# REM_Scan_v2.net
KiCad netlist of a schematic drawn in EAGLE
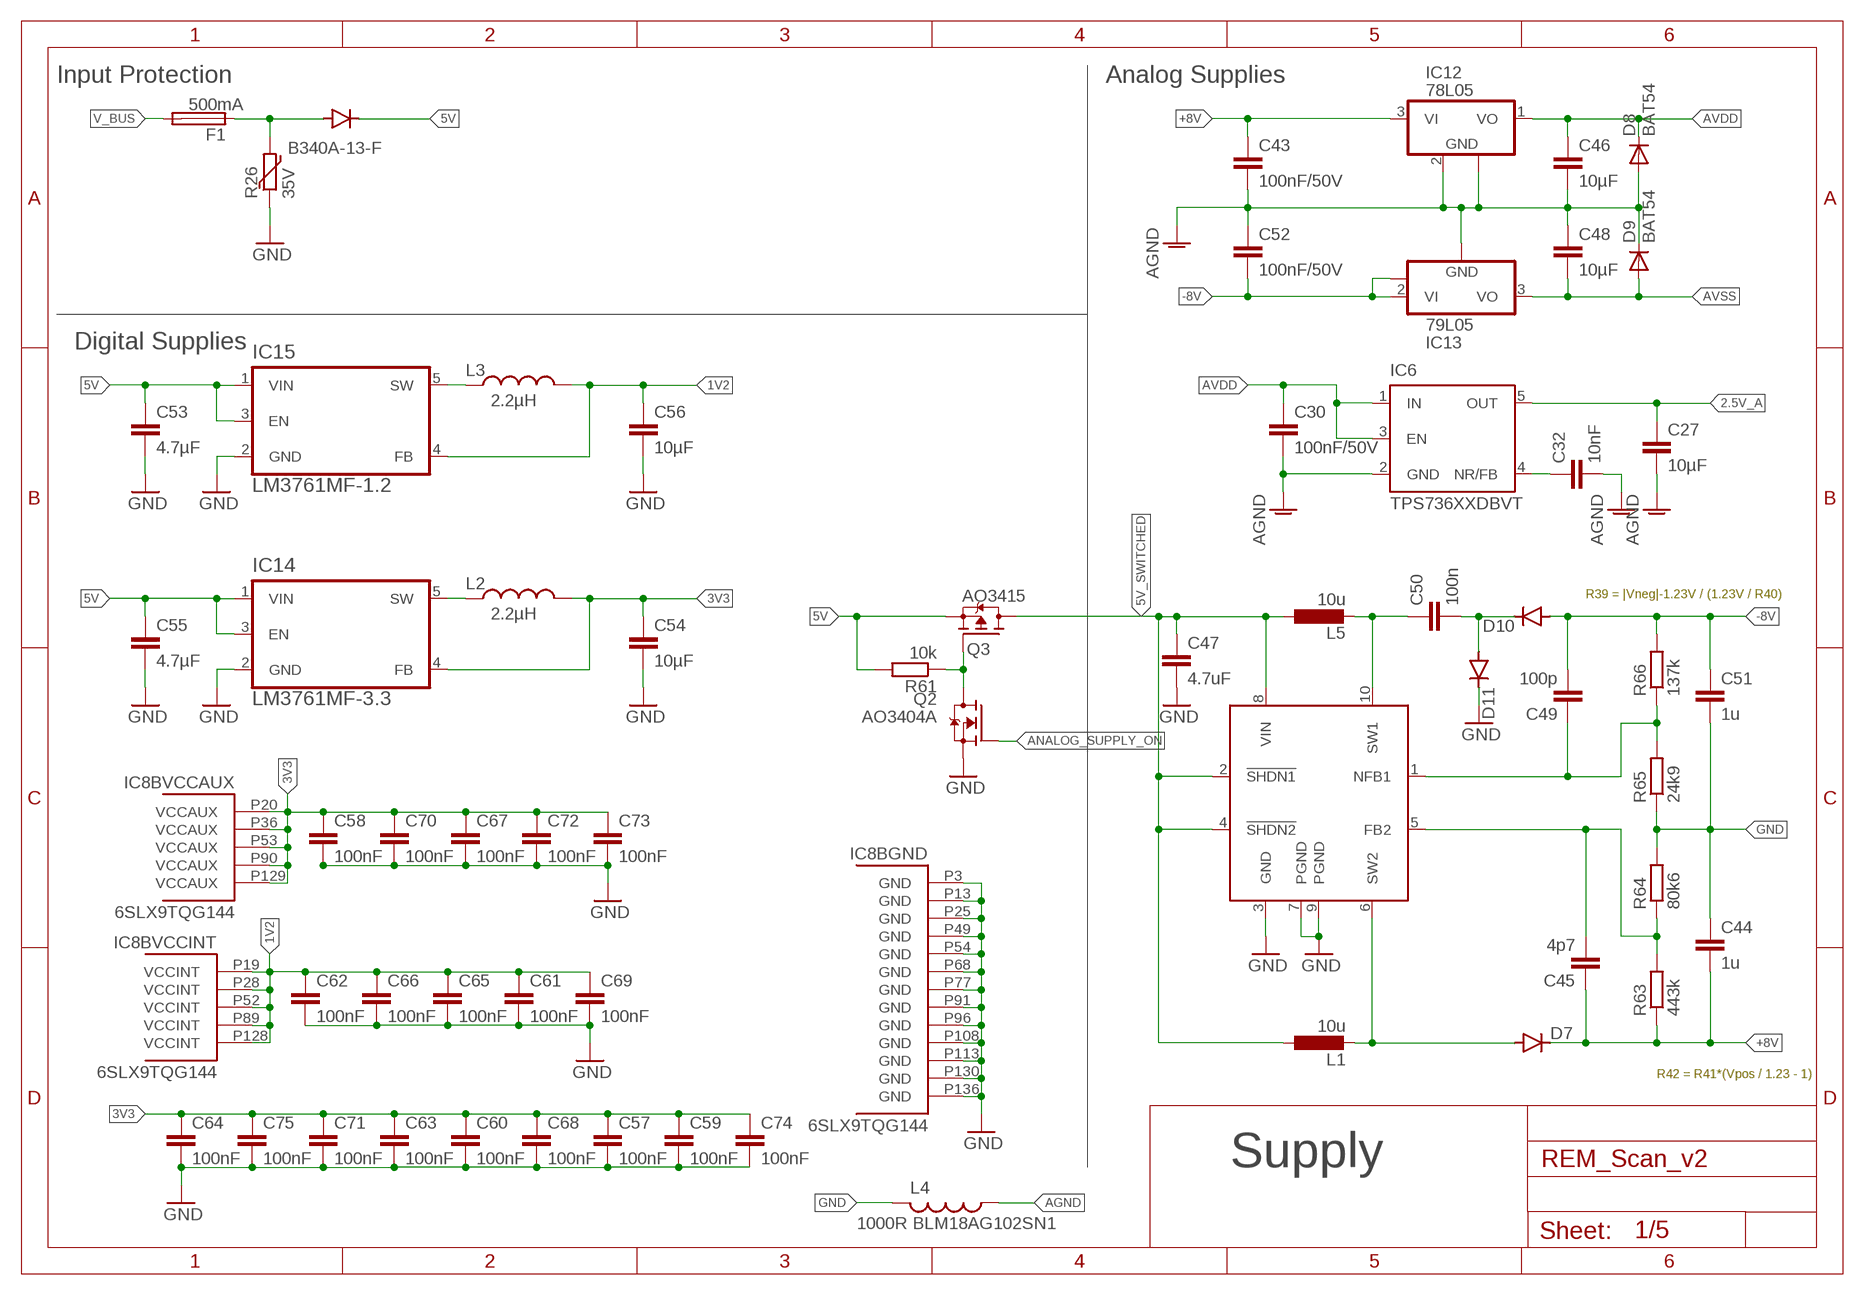
[diagram p0: schematic, sheet 1]
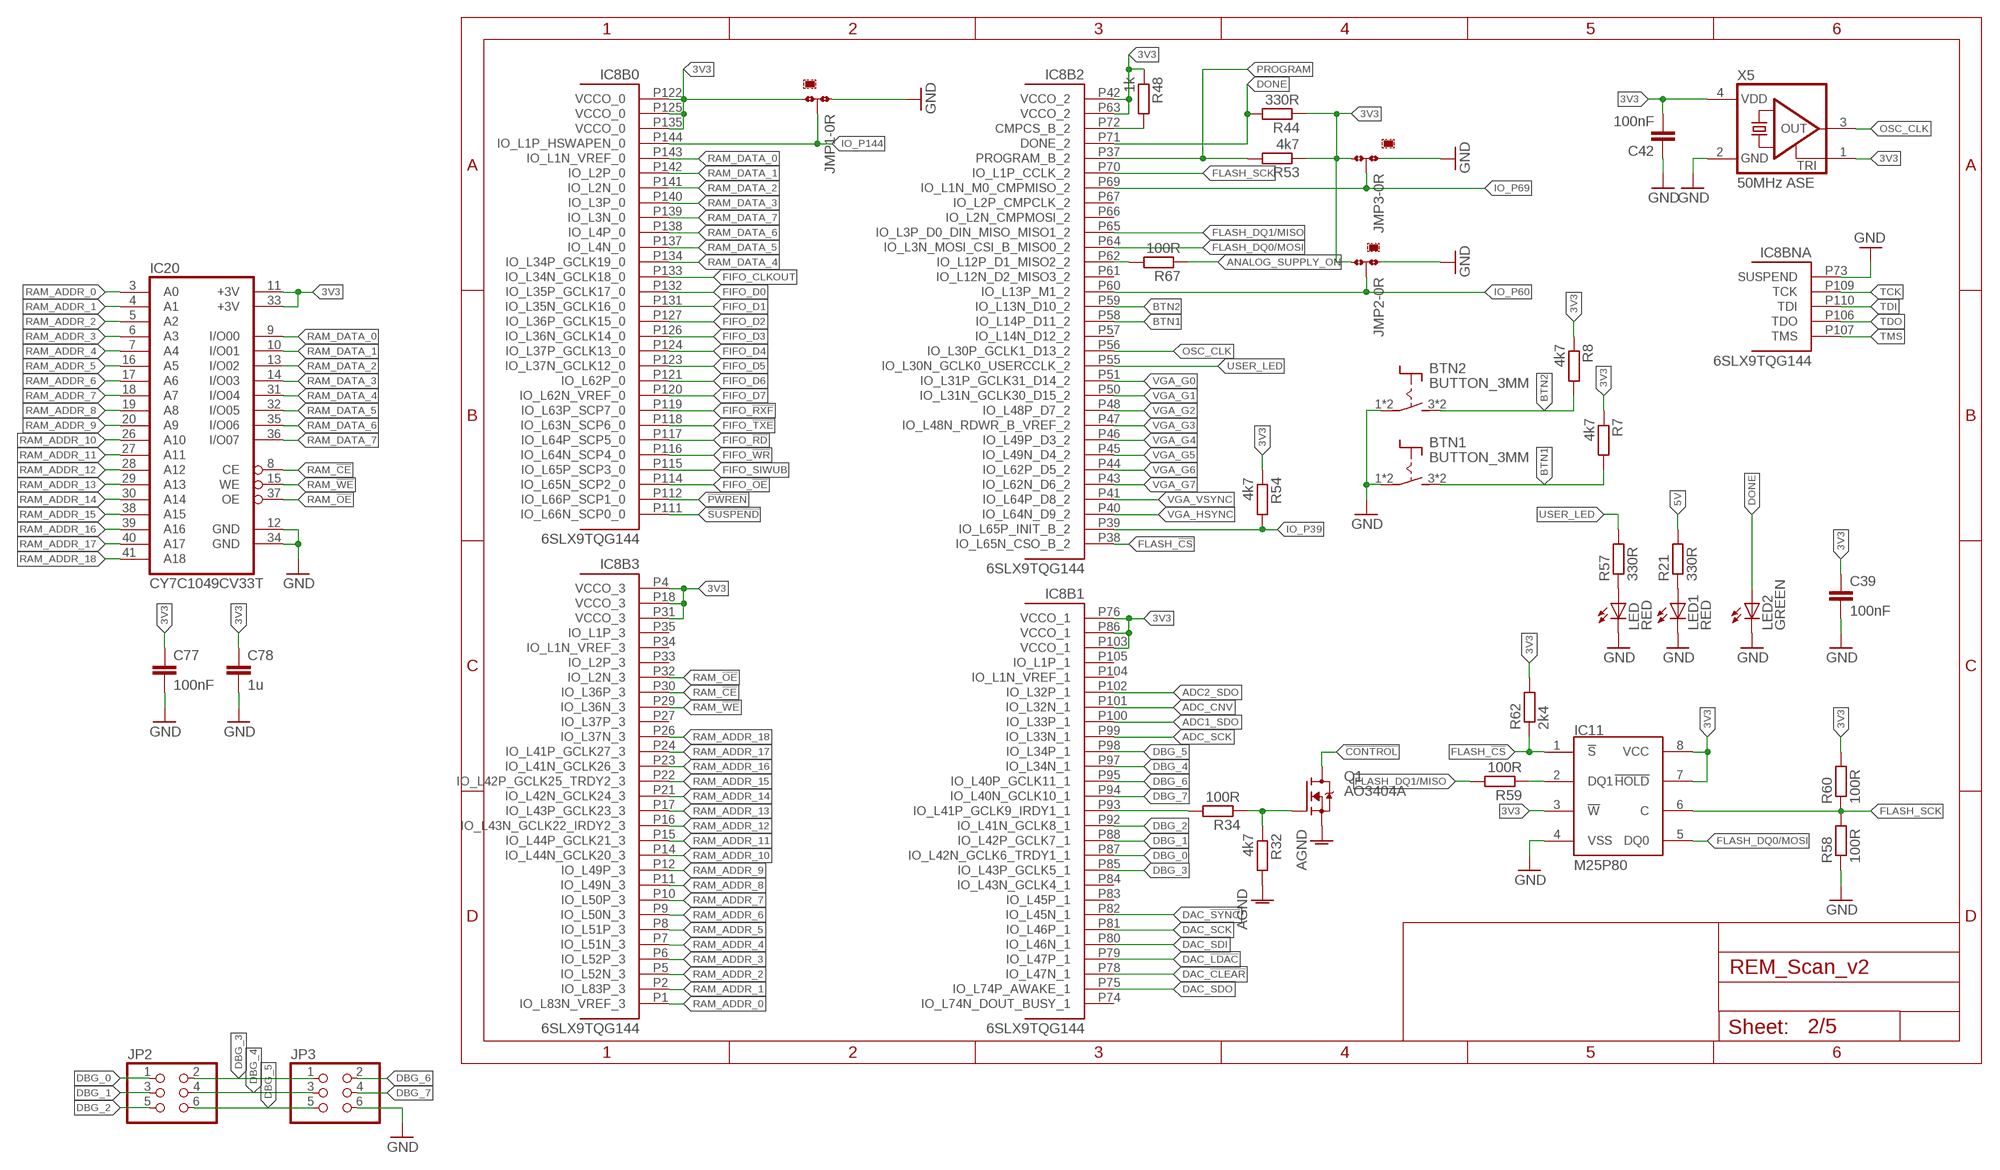
[diagram p1: schematic, sheet 2]
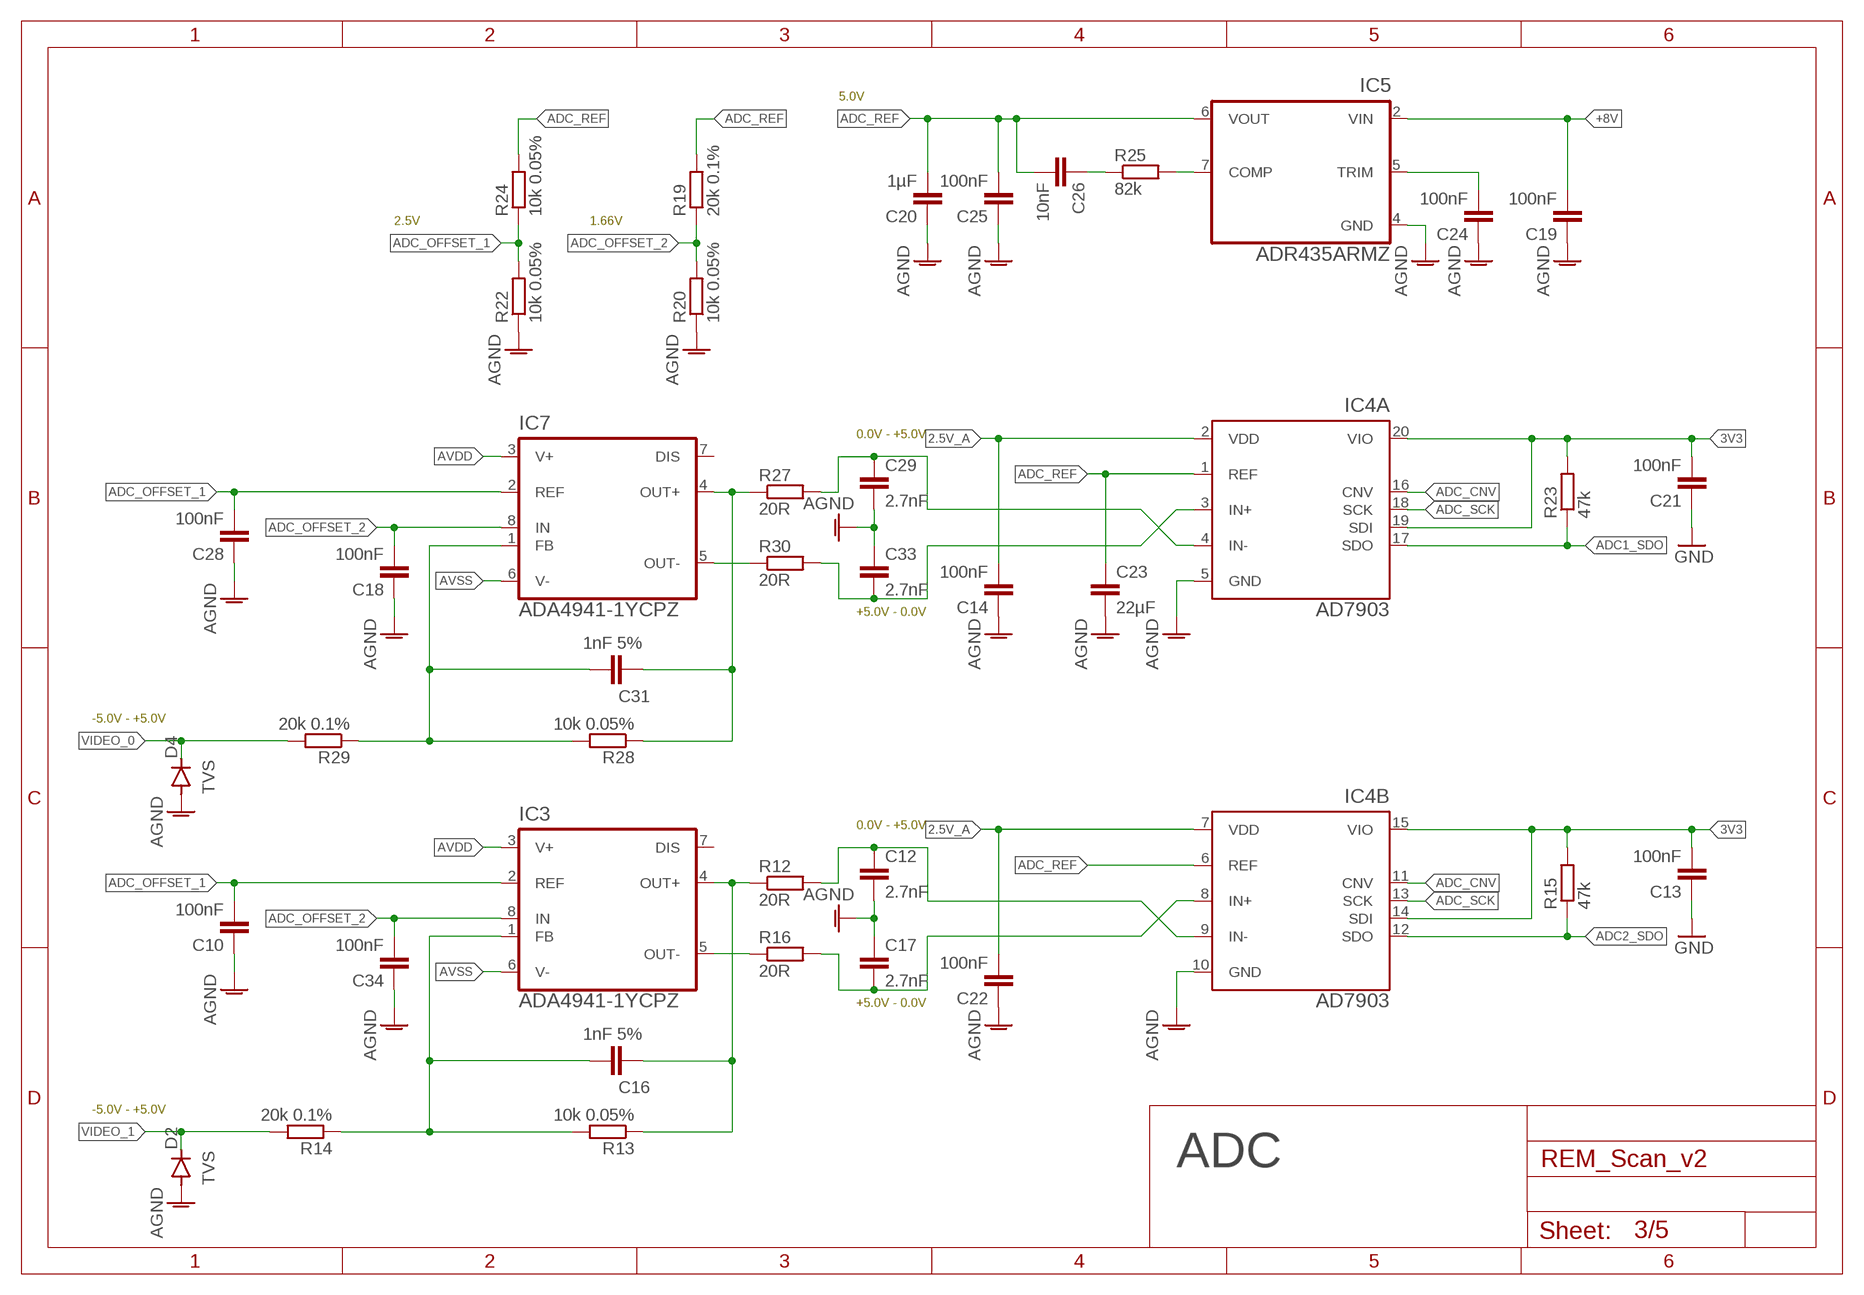
[diagram p2: schematic, sheet 3]
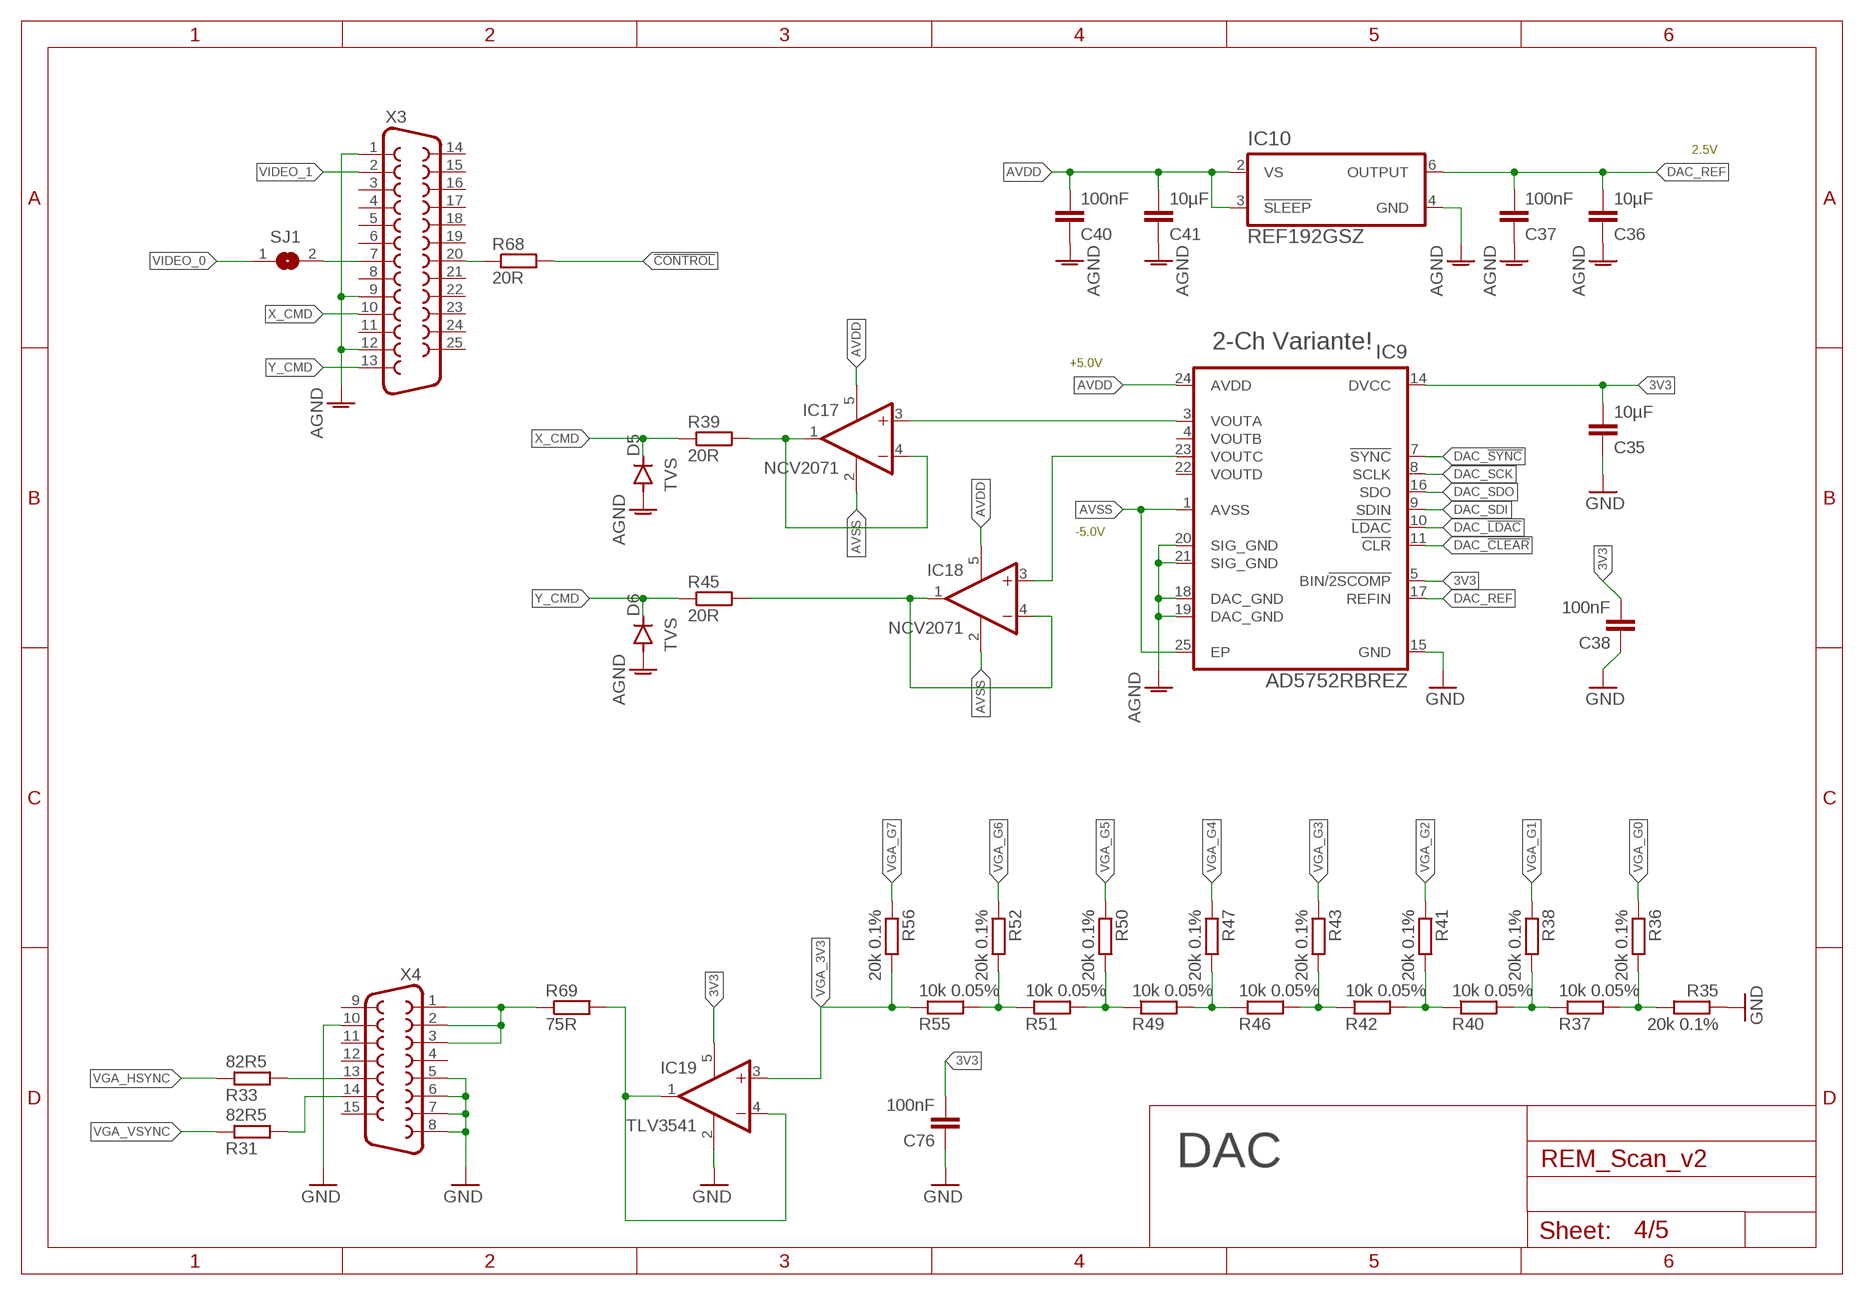
[diagram p3: schematic, sheet 4]
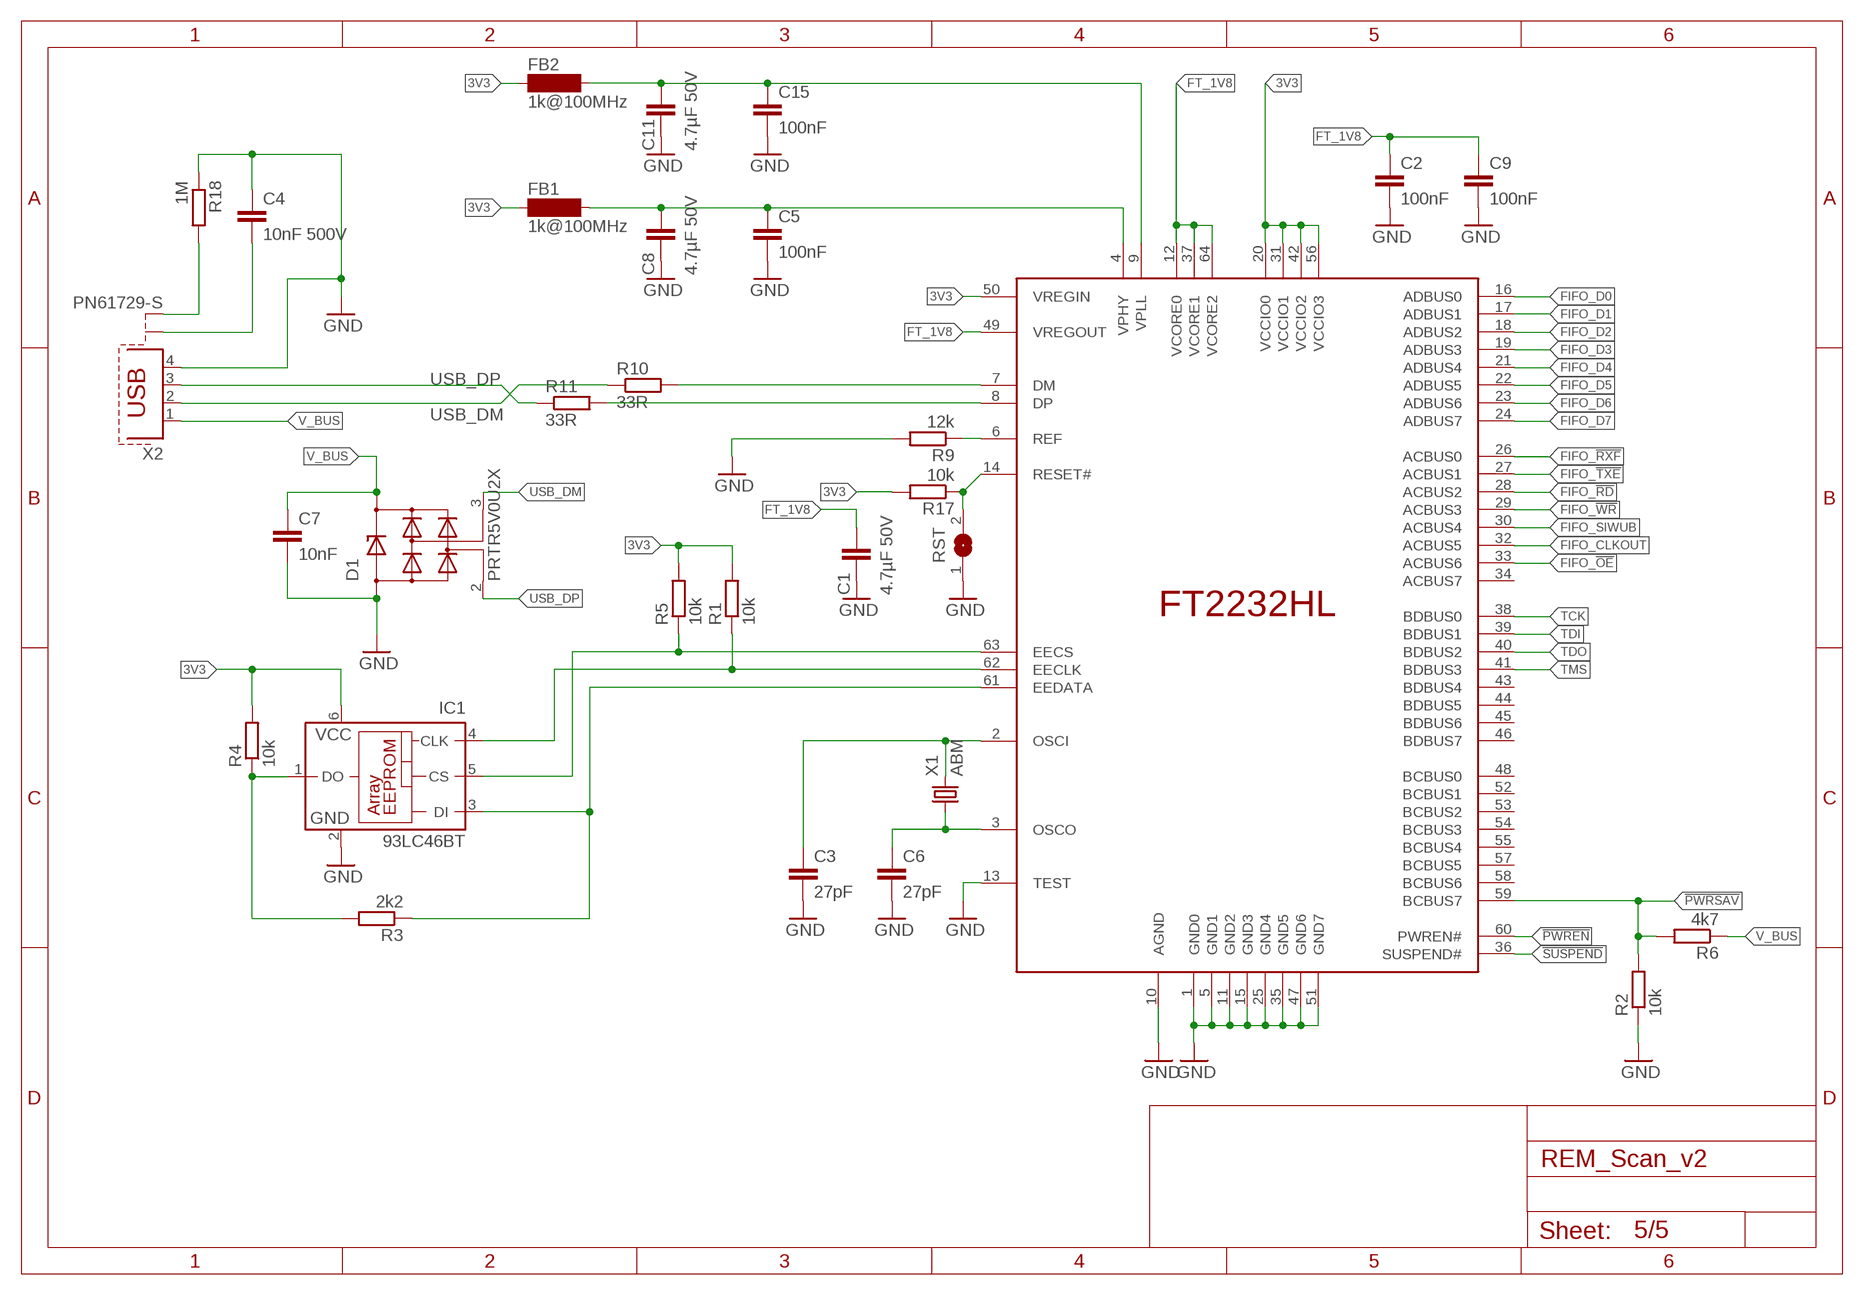
[diagram p4: schematic, sheet 5]

(export (version "E")
  (design (tool "Eeschema 10.0.6"))
  (components
    (comp (ref "C27")
      (value "10µF")
      (footprint "eagle-import:C0603")
      (libsource (lib "eagle-import") (part "C-EUC0603"))
    )
    (comp (ref "C30")
      (value "100nF/50V")
      (footprint "eagle-import:C0603")
      (libsource (lib "eagle-import") (part "C-EUC0603"))
    )
    (comp (ref "C32")
      (value "10nF")
      (footprint "eagle-import:C0603")
      (libsource (lib "eagle-import") (part "C-EUC0603"))
    )
    (comp (ref "C43")
      (value "100nF/50V")
      (footprint "eagle-import:C0603")
      (libsource (lib "eagle-import") (part "C-EUC0603"))
    )
    (comp (ref "C44")
      (value "1u")
      (footprint "eagle-import:C1206")
      (libsource (lib "eagle-import") (part "rcl_334_C-EUC1206"))
    )
    (comp (ref "C45")
      (value "4p7")
      (footprint "eagle-import:C0603")
      (libsource (lib "eagle-import") (part "rcl_334_C-EUC0603"))
    )
    (comp (ref "C46")
      (value "10µF")
      (footprint "eagle-import:C0603")
      (libsource (lib "eagle-import") (part "C-EUC0603"))
    )
    (comp (ref "C47")
      (value "4.7uF")
      (footprint "eagle-import:C3225")
      (libsource (lib "eagle-import") (part "C-EUC3225"))
    )
    (comp (ref "C48")
      (value "10µF")
      (footprint "eagle-import:C0603")
      (libsource (lib "eagle-import") (part "C-EUC0603"))
    )
    (comp (ref "C49")
      (value "100p")
      (footprint "eagle-import:C0603")
      (libsource (lib "eagle-import") (part "rcl_334_C-EUC0603"))
    )
    (comp (ref "C50")
      (value "100n")
      (footprint "eagle-import:C0603")
      (libsource (lib "eagle-import") (part "rcl_334_C-EUC0603"))
    )
    (comp (ref "C51")
      (value "1u")
      (footprint "eagle-import:C1206")
      (libsource (lib "eagle-import") (part "rcl_334_C-EUC1206"))
    )
    (comp (ref "C52")
      (value "100nF/50V")
      (footprint "eagle-import:C0603")
      (libsource (lib "eagle-import") (part "C-EUC0603"))
    )
    (comp (ref "C53")
      (value "4.7µF")
      (footprint "eagle-import:C0603")
      (libsource (lib "eagle-import") (part "C-EUC0603"))
    )
    (comp (ref "C54")
      (value "10µF")
      (footprint "eagle-import:C0603")
      (libsource (lib "eagle-import") (part "C-EUC0603"))
    )
    (comp (ref "C55")
      (value "4.7µF")
      (footprint "eagle-import:C0603")
      (libsource (lib "eagle-import") (part "C-EUC0603"))
    )
    (comp (ref "C56")
      (value "10µF")
      (footprint "eagle-import:C0603")
      (libsource (lib "eagle-import") (part "C-EUC0603"))
    )
    (comp (ref "C57")
      (value "100nF")
      (footprint "eagle-import:C0603")
      (libsource (lib "eagle-import") (part "C-EUC0603"))
    )
    (comp (ref "C58")
      (value "100nF")
      (footprint "eagle-import:C0603")
      (libsource (lib "eagle-import") (part "C-EUC0603"))
    )
    (comp (ref "C59")
      (value "100nF")
      (footprint "eagle-import:C0603")
      (libsource (lib "eagle-import") (part "C-EUC0603"))
    )
    (comp (ref "C60")
      (value "100nF")
      (footprint "eagle-import:C0603")
      (libsource (lib "eagle-import") (part "C-EUC0603"))
    )
    (comp (ref "C61")
      (value "100nF")
      (footprint "eagle-import:C0603")
      (libsource (lib "eagle-import") (part "C-EUC0603"))
    )
    (comp (ref "C62")
      (value "100nF")
      (footprint "eagle-import:C0603")
      (libsource (lib "eagle-import") (part "C-EUC0603"))
    )
    (comp (ref "C63")
      (value "100nF")
      (footprint "eagle-import:C0603")
      (libsource (lib "eagle-import") (part "C-EUC0603"))
    )
    (comp (ref "C64")
      (value "100nF")
      (footprint "eagle-import:C0603")
      (libsource (lib "eagle-import") (part "C-EUC0603"))
    )
    (comp (ref "C65")
      (value "100nF")
      (footprint "eagle-import:C0603")
      (libsource (lib "eagle-import") (part "C-EUC0603"))
    )
    (comp (ref "C66")
      (value "100nF")
      (footprint "eagle-import:C0603")
      (libsource (lib "eagle-import") (part "C-EUC0603"))
    )
    (comp (ref "C67")
      (value "100nF")
      (footprint "eagle-import:C0603")
      (libsource (lib "eagle-import") (part "C-EUC0603"))
    )
    (comp (ref "C68")
      (value "100nF")
      (footprint "eagle-import:C0603")
      (libsource (lib "eagle-import") (part "C-EUC0603"))
    )
    (comp (ref "C69")
      (value "100nF")
      (footprint "eagle-import:C0603")
      (libsource (lib "eagle-import") (part "C-EUC0603"))
    )
    (comp (ref "C70")
      (value "100nF")
      (footprint "eagle-import:C0603")
      (libsource (lib "eagle-import") (part "C-EUC0603"))
    )
    (comp (ref "C71")
      (value "100nF")
      (footprint "eagle-import:C0603")
      (libsource (lib "eagle-import") (part "C-EUC0603"))
    )
    (comp (ref "C72")
      (value "100nF")
      (footprint "eagle-import:C0603")
      (libsource (lib "eagle-import") (part "C-EUC0603"))
    )
    (comp (ref "C73")
      (value "100nF")
      (footprint "eagle-import:C0603")
      (libsource (lib "eagle-import") (part "C-EUC0603"))
    )
    (comp (ref "C74")
      (value "100nF")
      (footprint "eagle-import:C0603")
      (libsource (lib "eagle-import") (part "C-EUC0603"))
    )
    (comp (ref "C75")
      (value "100nF")
      (footprint "eagle-import:C0603")
      (libsource (lib "eagle-import") (part "C-EUC0603"))
    )
    (comp (ref "D3")
      (value "B340A-13-F")
      (footprint "eagle-import:DO214AA")
      (libsource (lib "eagle-import") (part "diode_210_DIODE-DO214AA"))
    )
    (comp (ref "D7")
      (value "DIODE-SOD323-W")
      (footprint "eagle-import:SOD323-W")
      (libsource (lib "eagle-import") (part "diode_210_DIODE-SOD323-W"))
    )
    (comp (ref "D8")
      (value "BAT54")
      (footprint "eagle-import:SOD323-W")
      (libsource (lib "eagle-import") (part "DIODE-SOD323-W"))
    )
    (comp (ref "D9")
      (value "BAT54")
      (footprint "eagle-import:SOD323-W")
      (libsource (lib "eagle-import") (part "DIODE-SOD323-W"))
    )
    (comp (ref "D10")
      (value "DIODE-SOD323-W")
      (footprint "eagle-import:SOD323-W")
      (libsource (lib "eagle-import") (part "diode_210_DIODE-SOD323-W"))
    )
    (comp (ref "D11")
      (value "DIODE-SOD323-W")
      (footprint "eagle-import:SOD323-W")
      (libsource (lib "eagle-import") (part "diode_210_DIODE-SOD323-W"))
    )
    (comp (ref "F1")
      (value "500mA")
      (footprint "eagle-import:1812")
      (libsource (lib "eagle-import") (part "FUSE1812"))
    )
    (comp (ref "IC6")
      (value "TPS736XXDBVT")
      (footprint "eagle-import:SOT23-DBV")
      (libsource (lib "eagle-import") (part "TPS736XXDBVT"))
    )
    (comp (ref "IC8")
      (value "6SLX9TQG144")
      (footprint "eagle-import:TQ144")
      (fields (field (name "DIGIKEY") "122-1747-ND"))
      (libsource (lib "eagle-import") (part "6SLX9TQG144"))
    )
    (comp (ref "IC12")
      (value "78L05")
      (footprint "eagle-import:SOT89")
      (libsource (lib "eagle-import") (part "78LF05"))
    )
    (comp (ref "IC13")
      (value "79L05")
      (footprint "eagle-import:SOT89")
      (libsource (lib "eagle-import") (part "79L"))
    )
    (comp (ref "IC14")
      (value "LM3761MF-3.3")
      (footprint "eagle-import:SOT95P284X122-5N")
      (libsource (lib "eagle-import") (part "LM3671"))
    )
    (comp (ref "IC15")
      (value "LM3761MF-1.2")
      (footprint "eagle-import:SOT95P284X122-5N")
      (libsource (lib "eagle-import") (part "LM3671"))
    )
    (comp (ref "IC16")
      (value "LT1945")
      (footprint "eagle-import:MSOP10")
      (libsource (lib "eagle-import") (part "LT1945"))
    )
    (comp (ref "L1")
      (value "10u")
      (footprint "eagle-import:L3225P")
      (libsource (lib "eagle-import") (part "L-EUL3225P"))
    )
    (comp (ref "L2")
      (value "2.2µH")
      (footprint "eagle-import:SO3314")
      (libsource (lib "eagle-import") (part "DO3314"))
    )
    (comp (ref "L3")
      (value "2.2µH")
      (footprint "eagle-import:SO3314")
      (libsource (lib "eagle-import") (part "DO3314"))
    )
    (comp (ref "L4")
      (value "1000R BLM18AG102SN1")
      (footprint "eagle-import:L2012C")
      (libsource (lib "eagle-import") (part "L-USL2012C"))
    )
    (comp (ref "L5")
      (value "10u")
      (footprint "eagle-import:L3225P")
      (libsource (lib "eagle-import") (part "L-EUL3225P"))
    )
    (comp (ref "Q2")
      (value "AO3404A")
      (footprint "eagle-import:SOT23")
      (libsource (lib "eagle-import") (part "N-MOSFET-SOT23-3"))
    )
    (comp (ref "Q3")
      (value "AO3415")
      (footprint "eagle-import:SOT95P280X130-3N")
      (fields
        (field (name "MPN") "TSM2311CX")
        (field (name "MPN_1") "AO3415")
        (field (name "SUPPLIER") "PUOLOP")
      )
      (libsource (lib "eagle-import") (part "TSM2311CX"))
    )
    (comp (ref "R26")
      (value "35V")
      (footprint "eagle-import:R1206")
      (libsource (lib "eagle-import") (part "MOV-EU_1206"))
    )
    (comp (ref "R61")
      (value "10k")
      (footprint "eagle-import:R0603")
      (libsource (lib "eagle-import") (part "rcl_334_R-EU_R0603"))
    )
    (comp (ref "R63")
      (value "443k")
      (footprint "eagle-import:R0603")
      (libsource (lib "eagle-import") (part "rcl_334_R-EU_R0603"))
    )
    (comp (ref "R64")
      (value "80k6")
      (footprint "eagle-import:R0603")
      (libsource (lib "eagle-import") (part "rcl_334_R-EU_R0603"))
    )
    (comp (ref "R65")
      (value "24k9")
      (footprint "eagle-import:R0603")
      (libsource (lib "eagle-import") (part "rcl_334_R-EU_R0603"))
    )
    (comp (ref "R66")
      (value "137k")
      (footprint "eagle-import:R0603")
      (libsource (lib "eagle-import") (part "rcl_334_R-EU_R0603"))
    )
    (comp (ref "C10")
      (value "100nF")
      (footprint "eagle-import:C0603")
      (libsource (lib "eagle-import") (part "C-EUC0603"))
    )
    (comp (ref "C12")
      (value "2.7nF")
      (footprint "eagle-import:C0603K")
      (libsource (lib "eagle-import") (part "C-EUC0603K"))
    )
    (comp (ref "C13")
      (value "100nF")
      (footprint "eagle-import:C0603")
      (libsource (lib "eagle-import") (part "C-EUC0603"))
    )
    (comp (ref "C14")
      (value "100nF")
      (footprint "eagle-import:C0603")
      (libsource (lib "eagle-import") (part "C-EUC0603"))
    )
    (comp (ref "C16")
      (value "1nF 5%")
      (footprint "eagle-import:C0603")
      (libsource (lib "eagle-import") (part "C-EUC0603"))
    )
    (comp (ref "C17")
      (value "2.7nF")
      (footprint "eagle-import:C0603K")
      (libsource (lib "eagle-import") (part "C-EUC0603K"))
    )
    (comp (ref "C18")
      (value "100nF")
      (footprint "eagle-import:C0603")
      (libsource (lib "eagle-import") (part "C-EUC0603"))
    )
    (comp (ref "C19")
      (value "100nF")
      (footprint "eagle-import:C0603")
      (libsource (lib "eagle-import") (part "C-EUC0603"))
    )
    (comp (ref "C20")
      (value "1µF")
      (footprint "eagle-import:C0603")
      (libsource (lib "eagle-import") (part "C-EUC0603"))
    )
    (comp (ref "C21")
      (value "100nF")
      (footprint "eagle-import:C0603")
      (libsource (lib "eagle-import") (part "C-EUC0603"))
    )
    (comp (ref "C22")
      (value "100nF")
      (footprint "eagle-import:C0603")
      (libsource (lib "eagle-import") (part "C-EUC0603"))
    )
    (comp (ref "C23")
      (value "22µF")
      (footprint "eagle-import:C0805K")
      (libsource (lib "eagle-import") (part "C-EUC0805K"))
    )
    (comp (ref "C24")
      (value "100nF")
      (footprint "eagle-import:C0603")
      (libsource (lib "eagle-import") (part "C-EUC0603"))
    )
    (comp (ref "C25")
      (value "100nF")
      (footprint "eagle-import:C0603")
      (libsource (lib "eagle-import") (part "C-EUC0603"))
    )
    (comp (ref "C26")
      (value "10nF")
      (footprint "eagle-import:C0603")
      (libsource (lib "eagle-import") (part "C-EUC0603"))
    )
    (comp (ref "C28")
      (value "100nF")
      (footprint "eagle-import:C0603")
      (libsource (lib "eagle-import") (part "C-EUC0603"))
    )
    (comp (ref "C29")
      (value "2.7nF")
      (footprint "eagle-import:C0603K")
      (libsource (lib "eagle-import") (part "C-EUC0603K"))
    )
    (comp (ref "C31")
      (value "1nF 5%")
      (footprint "eagle-import:C0603")
      (libsource (lib "eagle-import") (part "C-EUC0603"))
    )
    (comp (ref "C33")
      (value "2.7nF")
      (footprint "eagle-import:C0603K")
      (libsource (lib "eagle-import") (part "C-EUC0603K"))
    )
    (comp (ref "C34")
      (value "100nF")
      (footprint "eagle-import:C0603")
      (libsource (lib "eagle-import") (part "C-EUC0603"))
    )
    (comp (ref "D2")
      (value "TVS")
      (footprint "eagle-import:SOD123")
      (libsource (lib "eagle-import") (part "diode_210_DIODE-SOD123"))
    )
    (comp (ref "D4")
      (value "TVS")
      (footprint "eagle-import:SOD123")
      (libsource (lib "eagle-import") (part "diode_210_DIODE-SOD123"))
    )
    (comp (ref "IC3")
      (value "ADA4941-1YCPZ")
      (footprint "eagle-import:LFCSP_VD8_CP-8-2")
      (libsource (lib "eagle-import") (part "ADA4941-1YCPZ"))
    )
    (comp (ref "IC4")
      (value "AD7903")
      (footprint "eagle-import:RQ-20")
      (libsource (lib "eagle-import") (part "AD7903"))
    )
    (comp (ref "IC5")
      (value "ADR435ARMZ")
      (footprint "eagle-import:MSOP08")
      (libsource (lib "eagle-import") (part "ADR435ARMZ"))
    )
    (comp (ref "IC7")
      (value "ADA4941-1YCPZ")
      (footprint "eagle-import:LFCSP_VD8_CP-8-2")
      (libsource (lib "eagle-import") (part "ADA4941-1YCPZ"))
    )
    (comp (ref "R12")
      (value "20R")
      (footprint "eagle-import:R0603")
      (libsource (lib "eagle-import") (part "R-EU_R0603"))
    )
    (comp (ref "R13")
      (value "10k 0.05%")
      (footprint "eagle-import:R0603")
      (libsource (lib "eagle-import") (part "R-EU_R0603"))
    )
    (comp (ref "R14")
      (value "20k 0.1%")
      (footprint "eagle-import:R0603")
      (libsource (lib "eagle-import") (part "R-EU_R0603"))
    )
    (comp (ref "R15")
      (value "47k")
      (footprint "eagle-import:R0603")
      (libsource (lib "eagle-import") (part "R-EU_R0603"))
    )
    (comp (ref "R16")
      (value "20R")
      (footprint "eagle-import:R0603")
      (libsource (lib "eagle-import") (part "R-EU_R0603"))
    )
    (comp (ref "R19")
      (value "20k 0.1%")
      (footprint "eagle-import:R0603")
      (libsource (lib "eagle-import") (part "R-EU_R0603"))
    )
    (comp (ref "R20")
      (value "10k 0.05%")
      (footprint "eagle-import:R0603")
      (libsource (lib "eagle-import") (part "R-EU_R0603"))
    )
    (comp (ref "R22")
      (value "10k 0.05%")
      (footprint "eagle-import:R0603")
      (libsource (lib "eagle-import") (part "R-EU_R0603"))
    )
    (comp (ref "R23")
      (value "47k")
      (footprint "eagle-import:R0603")
      (libsource (lib "eagle-import") (part "R-EU_R0603"))
    )
    (comp (ref "R24")
      (value "10k 0.05%")
      (footprint "eagle-import:R0603")
      (libsource (lib "eagle-import") (part "R-EU_R0603"))
    )
    (comp (ref "R25")
      (value "82k")
      (footprint "eagle-import:R0603")
      (libsource (lib "eagle-import") (part "R-EU_R0603"))
    )
    (comp (ref "R27")
      (value "20R")
      (footprint "eagle-import:R0603")
      (libsource (lib "eagle-import") (part "R-EU_R0603"))
    )
    (comp (ref "R28")
      (value "10k 0.05%")
      (footprint "eagle-import:R0603")
      (libsource (lib "eagle-import") (part "R-EU_R0603"))
    )
    (comp (ref "R29")
      (value "20k 0.1%")
      (footprint "eagle-import:R0603")
      (libsource (lib "eagle-import") (part "R-EU_R0603"))
    )
    (comp (ref "R30")
      (value "20R")
      (footprint "eagle-import:R0603")
      (libsource (lib "eagle-import") (part "R-EU_R0603"))
    )
    (comp (ref "BTN1")
      (value "BUTTON_3MM")
      (footprint "eagle-import:BUTTON_3MM")
      (libsource (lib "eagle-import") (part "BUTTON_3MM"))
    )
    (comp (ref "BTN2")
      (value "BUTTON_3MM")
      (footprint "eagle-import:BUTTON_3MM")
      (libsource (lib "eagle-import") (part "BUTTON_3MM"))
    )
    (comp (ref "C39")
      (value "100nF")
      (footprint "eagle-import:C0603")
      (libsource (lib "eagle-import") (part "C-EUC0603"))
    )
    (comp (ref "C42")
      (value "100nF")
      (footprint "eagle-import:C0603")
      (libsource (lib "eagle-import") (part "C-EUC0603"))
    )
    (comp (ref "C77")
      (value "100nF")
      (footprint "eagle-import:C0603")
      (libsource (lib "eagle-import") (part "C-EUC0603"))
    )
    (comp (ref "C78")
      (value "1u")
      (footprint "eagle-import:C1206")
      (libsource (lib "eagle-import") (part "rcl_334_C-EUC1206"))
    )
    (comp (ref "IC11")
      (value "M25P80")
      (footprint "eagle-import:SO-08")
      (libsource (lib "eagle-import") (part "M25P80"))
    )
    (comp (ref "IC20")
      (value "CY7C1049CV33T")
      (footprint "eagle-import:TSOPII-Z44")
      (libsource (lib "eagle-import") (part "CY7C1049CV33T"))
    )
    (comp (ref "JMP1")
      (value "1k")
      (footprint "eagle-import:A0R-JMP")
      (libsource (lib "eagle-import") (part "0R-JUMPA"))
    )
    (comp (ref "JMP2")
      (value "1k")
      (footprint "eagle-import:A0R-JMP")
      (libsource (lib "eagle-import") (part "0R-JUMPA"))
    )
    (comp (ref "JMP3")
      (value "1k")
      (footprint "eagle-import:A0R-JMP")
      (libsource (lib "eagle-import") (part "0R-JUMPA"))
    )
    (comp (ref "JP2")
      (value "PINHD-2X3_2.54")
      (footprint "eagle-import:2X03")
      (libsource (lib "eagle-import") (part "PINHD-2X3_2.54"))
    )
    (comp (ref "JP3")
      (value "PINHD-2X3_2.54")
      (footprint "eagle-import:2X03")
      (libsource (lib "eagle-import") (part "PINHD-2X3_2.54"))
    )
    (comp (ref "LED")
      (value "RED")
      (footprint "eagle-import:CHIP-LED0603")
      (libsource (lib "eagle-import") (part "LEDCHIP-LED0603"))
    )
    (comp (ref "LED1")
      (value "RED")
      (footprint "eagle-import:CHIP-LED0603")
      (libsource (lib "eagle-import") (part "LEDCHIP-LED0603"))
    )
    (comp (ref "LED2")
      (value "GREEN")
      (footprint "eagle-import:CHIP-LED0603")
      (libsource (lib "eagle-import") (part "LEDCHIP-LED0603"))
    )
    (comp (ref "Q1")
      (value "AO3404A")
      (footprint "eagle-import:SOT23")
      (libsource (lib "eagle-import") (part "N-MOSFET-SOT23-3"))
    )
    (comp (ref "R7")
      (value "4k7")
      (footprint "eagle-import:R0603")
      (libsource (lib "eagle-import") (part "R-EU_R0603"))
    )
    (comp (ref "R8")
      (value "4k7")
      (footprint "eagle-import:R0603")
      (libsource (lib "eagle-import") (part "R-EU_R0603"))
    )
    (comp (ref "R21")
      (value "330R")
      (footprint "eagle-import:R0603")
      (libsource (lib "eagle-import") (part "R-EU_R0603"))
    )
    (comp (ref "R32")
      (value "4k7")
      (footprint "eagle-import:R0603")
      (libsource (lib "eagle-import") (part "R-EU_R0603"))
    )
    (comp (ref "R34")
      (value "100R")
      (footprint "eagle-import:R0603")
      (libsource (lib "eagle-import") (part "R-EU_R0603"))
    )
    (comp (ref "R44")
      (value "330R")
      (footprint "eagle-import:R0603")
      (libsource (lib "eagle-import") (part "R-EU_R0603"))
    )
    (comp (ref "R48")
      (value "1k")
      (footprint "eagle-import:R0603")
      (libsource (lib "eagle-import") (part "R-EU_R0603"))
    )
    (comp (ref "R53")
      (value "4k7")
      (footprint "eagle-import:R0603")
      (libsource (lib "eagle-import") (part "R-EU_R0603"))
    )
    (comp (ref "R54")
      (value "4k7")
      (footprint "eagle-import:R0603")
      (libsource (lib "eagle-import") (part "R-EU_R0603"))
    )
    (comp (ref "R57")
      (value "330R")
      (footprint "eagle-import:R0603")
      (libsource (lib "eagle-import") (part "R-EU_R0603"))
    )
    (comp (ref "R58")
      (value "100R")
      (footprint "eagle-import:R0603")
      (libsource (lib "eagle-import") (part "R-EU_R0603"))
    )
    (comp (ref "R59")
      (value "100R")
      (footprint "eagle-import:R0603")
      (libsource (lib "eagle-import") (part "R-EU_R0603"))
    )
    (comp (ref "R60")
      (value "100R")
      (footprint "eagle-import:R0603")
      (libsource (lib "eagle-import") (part "R-EU_R0603"))
    )
    (comp (ref "R62")
      (value "2k4")
      (footprint "eagle-import:R0603")
      (libsource (lib "eagle-import") (part "R-EU_R0603"))
    )
    (comp (ref "R67")
      (value "100R")
      (footprint "eagle-import:R0603")
      (libsource (lib "eagle-import") (part "R-EU_R0603"))
    )
    (comp (ref "X5")
      (value "50MHz ASE")
      (footprint "eagle-import:ASE")
      (libsource (lib "eagle-import") (part "ASE"))
    )
    (comp (ref "C1")
      (value "4.7µF 50V")
      (footprint "eagle-import:C0805")
      (libsource (lib "eagle-import") (part "C-EUC0805"))
    )
    (comp (ref "C2")
      (value "100nF")
      (footprint "eagle-import:C0603")
      (libsource (lib "eagle-import") (part "rcl_334_C-EUC0603"))
    )
    (comp (ref "C3")
      (value "27pF")
      (footprint "eagle-import:C0603")
      (libsource (lib "eagle-import") (part "rcl_334_C-EUC0603"))
    )
    (comp (ref "C4")
      (value "10nF 500V")
      (footprint "eagle-import:C0805")
      (libsource (lib "eagle-import") (part "C-EUC0805"))
    )
    (comp (ref "C5")
      (value "100nF")
      (footprint "eagle-import:C0603")
      (libsource (lib "eagle-import") (part "rcl_334_C-EUC0603"))
    )
    (comp (ref "C6")
      (value "27pF")
      (footprint "eagle-import:C0603")
      (libsource (lib "eagle-import") (part "rcl_334_C-EUC0603"))
    )
    (comp (ref "C7")
      (value "10nF")
      (footprint "eagle-import:C0603")
      (libsource (lib "eagle-import") (part "C-EUC0603"))
    )
    (comp (ref "C8")
      (value "4.7µF 50V")
      (footprint "eagle-import:C0805")
      (libsource (lib "eagle-import") (part "C-EUC0805"))
    )
    (comp (ref "C9")
      (value "100nF")
      (footprint "eagle-import:C0603")
      (libsource (lib "eagle-import") (part "rcl_334_C-EUC0603"))
    )
    (comp (ref "C11")
      (value "4.7µF 50V")
      (footprint "eagle-import:C0805")
      (libsource (lib "eagle-import") (part "C-EUC0805"))
    )
    (comp (ref "C15")
      (value "100nF")
      (footprint "eagle-import:C0603")
      (libsource (lib "eagle-import") (part "rcl_334_C-EUC0603"))
    )
    (comp (ref "D1")
      (value "PRTR5V0U2X")
      (footprint "eagle-import:SOT143")
      (libsource (lib "eagle-import") (part "PRTR5V0U2X"))
    )
    (comp (ref "FB1")
      (value "1k@100MHz")
      (footprint "eagle-import:SM-1206")
      (libsource (lib "eagle-import") (part "SM-1206"))
    )
    (comp (ref "FB2")
      (value "1k@100MHz")
      (footprint "eagle-import:SM-1206")
      (libsource (lib "eagle-import") (part "SM-1206"))
    )
    (comp (ref "IC1")
      (value "93LC46BT")
      (footprint "eagle-import:SOT23-6")
      (libsource (lib "eagle-import") (part "9376?BC"))
    )
    (comp (ref "IC2")
      (value "FT2232HL")
      (footprint "eagle-import:LQFP64")
      (libsource (lib "eagle-import") (part "FT2232HL"))
    )
    (comp (ref "R1")
      (value "10k")
      (footprint "eagle-import:R0603")
      (libsource (lib "eagle-import") (part "rcl_334_R-EU_R0603"))
    )
    (comp (ref "R2")
      (value "10k")
      (footprint "eagle-import:R0603")
      (libsource (lib "eagle-import") (part "rcl_334_R-EU_R0603"))
    )
    (comp (ref "R3")
      (value "2k2")
      (footprint "eagle-import:R0603")
      (libsource (lib "eagle-import") (part "rcl_334_R-EU_R0603"))
    )
    (comp (ref "R4")
      (value "10k")
      (footprint "eagle-import:R0603")
      (libsource (lib "eagle-import") (part "rcl_334_R-EU_R0603"))
    )
    (comp (ref "R5")
      (value "10k")
      (footprint "eagle-import:R0603")
      (libsource (lib "eagle-import") (part "rcl_334_R-EU_R0603"))
    )
    (comp (ref "R6")
      (value "4k7")
      (footprint "eagle-import:R0603")
      (libsource (lib "eagle-import") (part "rcl_334_R-EU_R0603"))
    )
    (comp (ref "R9")
      (value "12k")
      (footprint "eagle-import:R0603")
      (libsource (lib "eagle-import") (part "rcl_334_R-EU_R0603"))
    )
    (comp (ref "R10")
      (value "33R")
      (footprint "eagle-import:R0603")
      (libsource (lib "eagle-import") (part "R-EU_R0603"))
    )
    (comp (ref "R11")
      (value "33R")
      (footprint "eagle-import:R0603")
      (libsource (lib "eagle-import") (part "R-EU_R0603"))
    )
    (comp (ref "R17")
      (value "10k")
      (footprint "eagle-import:R0603")
      (libsource (lib "eagle-import") (part "rcl_334_R-EU_R0603"))
    )
    (comp (ref "R18")
      (value "1M")
      (footprint "eagle-import:R0603")
      (libsource (lib "eagle-import") (part "rcl_334_R-EU_R0603"))
    )
    (comp (ref "RST")
      (value "SJS")
      (footprint "eagle-import:SJS")
      (libsource (lib "eagle-import") (part "SJS"))
    )
    (comp (ref "X1")
      (value "ABM")
      (footprint "eagle-import:ASE")
      (libsource (lib "eagle-import") (part "ABM"))
    )
    (comp (ref "X2")
      (value "PN61729-S")
      (footprint "eagle-import:PN61729-S")
      (libsource (lib "eagle-import") (part "PN61729-S"))
    )
    (comp (ref "C35")
      (value "10µF")
      (footprint "eagle-import:C0603")
      (fields (field (name "FARNELL") "2497051"))
      (libsource (lib "eagle-import") (part "C-EUC0603"))
    )
    (comp (ref "C36")
      (value "10µF")
      (footprint "eagle-import:C0603")
      (fields (field (name "FARNELL") "2497051"))
      (libsource (lib "eagle-import") (part "C-EUC0603"))
    )
    (comp (ref "C37")
      (value "100nF")
      (footprint "eagle-import:C0603")
      (libsource (lib "eagle-import") (part "C-EUC0603"))
    )
    (comp (ref "C38")
      (value "100nF")
      (footprint "eagle-import:C0603")
      (libsource (lib "eagle-import") (part "C-EUC0603"))
    )
    (comp (ref "C40")
      (value "100nF")
      (footprint "eagle-import:C0603")
      (libsource (lib "eagle-import") (part "C-EUC0603"))
    )
    (comp (ref "C41")
      (value "10µF")
      (footprint "eagle-import:C0603")
      (fields (field (name "FARNELL") "2497051"))
      (libsource (lib "eagle-import") (part "C-EUC0603"))
    )
    (comp (ref "C76")
      (value "100nF")
      (footprint "eagle-import:C0603")
      (libsource (lib "eagle-import") (part "C-EUC0603"))
    )
    (comp (ref "D5")
      (value "TVS")
      (footprint "eagle-import:SOD123")
      (libsource (lib "eagle-import") (part "diode_210_DIODE-SOD123"))
    )
    (comp (ref "D6")
      (value "TVS")
      (footprint "eagle-import:SOD123")
      (libsource (lib "eagle-import") (part "diode_210_DIODE-SOD123"))
    )
    (comp (ref "IC9")
      (value "AD5752RBREZ")
      (footprint "eagle-import:SOP65P640X120-25N")
      (fields
        (field (name "MPN") "AD5754RBREZ")
        (field (name "FARNELL") "1786049")
        (field (name "MPN_1") "AD5752RBREZ")
      )
      (libsource (lib "eagle-import") (part "AD5754RBREZ"))
    )
    (comp (ref "IC10")
      (value "REF192GSZ")
      (footprint "eagle-import:SOIC127P600X175-8N")
      (libsource (lib "eagle-import") (part "REF192GSZ"))
    )
    (comp (ref "IC17")
      (value "NCV2071")
      (footprint "eagle-import:SOT23-5")
      (libsource (lib "eagle-import") (part "OPA-SOT23344N"))
    )
    (comp (ref "IC18")
      (value "NCV2071")
      (footprint "eagle-import:SOT23-5")
      (libsource (lib "eagle-import") (part "OPA-SOT23344N"))
    )
    (comp (ref "IC19")
      (value "TLV3541")
      (footprint "eagle-import:SOT23-5")
      (libsource (lib "eagle-import") (part "OPA-SOT23344N"))
    )
    (comp (ref "R31")
      (value "82R5")
      (footprint "eagle-import:R0603")
      (libsource (lib "eagle-import") (part "R-EU_R0603"))
    )
    (comp (ref "R33")
      (value "82R5")
      (footprint "eagle-import:R0603")
      (libsource (lib "eagle-import") (part "R-EU_R0603"))
    )
    (comp (ref "R35")
      (value "20k 0.1%")
      (footprint "eagle-import:R0603")
      (libsource (lib "eagle-import") (part "R-EU_R0603"))
    )
    (comp (ref "R36")
      (value "20k 0.1%")
      (footprint "eagle-import:R0603")
      (libsource (lib "eagle-import") (part "R-EU_R0603"))
    )
    (comp (ref "R37")
      (value "10k 0.05%")
      (footprint "eagle-import:R0603")
      (libsource (lib "eagle-import") (part "R-EU_R0603"))
    )
    (comp (ref "R38")
      (value "20k 0.1%")
      (footprint "eagle-import:R0603")
      (libsource (lib "eagle-import") (part "R-EU_R0603"))
    )
    (comp (ref "R39")
      (value "20R")
      (footprint "eagle-import:R0603")
      (libsource (lib "eagle-import") (part "R-EU_R0603"))
    )
    (comp (ref "R40")
      (value "10k 0.05%")
      (footprint "eagle-import:R0603")
      (libsource (lib "eagle-import") (part "R-EU_R0603"))
    )
    (comp (ref "R41")
      (value "20k 0.1%")
      (footprint "eagle-import:R0603")
      (libsource (lib "eagle-import") (part "R-EU_R0603"))
    )
    (comp (ref "R42")
      (value "10k 0.05%")
      (footprint "eagle-import:R0603")
      (libsource (lib "eagle-import") (part "R-EU_R0603"))
    )
    (comp (ref "R43")
      (value "20k 0.1%")
      (footprint "eagle-import:R0603")
      (libsource (lib "eagle-import") (part "R-EU_R0603"))
    )
    (comp (ref "R45")
      (value "20R")
      (footprint "eagle-import:R0603")
      (libsource (lib "eagle-import") (part "R-EU_R0603"))
    )
    (comp (ref "R46")
      (value "10k 0.05%")
      (footprint "eagle-import:R0603")
      (libsource (lib "eagle-import") (part "R-EU_R0603"))
    )
    (comp (ref "R47")
      (value "20k 0.1%")
      (footprint "eagle-import:R0603")
      (libsource (lib "eagle-import") (part "R-EU_R0603"))
    )
    (comp (ref "R49")
      (value "10k 0.05%")
      (footprint "eagle-import:R0603")
      (libsource (lib "eagle-import") (part "R-EU_R0603"))
    )
    (comp (ref "R50")
      (value "20k 0.1%")
      (footprint "eagle-import:R0603")
      (libsource (lib "eagle-import") (part "R-EU_R0603"))
    )
    (comp (ref "R51")
      (value "10k 0.05%")
      (footprint "eagle-import:R0603")
      (libsource (lib "eagle-import") (part "R-EU_R0603"))
    )
    (comp (ref "R52")
      (value "20k 0.1%")
      (footprint "eagle-import:R0603")
      (libsource (lib "eagle-import") (part "R-EU_R0603"))
    )
    (comp (ref "R55")
      (value "10k 0.05%")
      (footprint "eagle-import:R0603")
      (libsource (lib "eagle-import") (part "R-EU_R0603"))
    )
    (comp (ref "R56")
      (value "20k 0.1%")
      (footprint "eagle-import:R0603")
      (libsource (lib "eagle-import") (part "R-EU_R0603"))
    )
    (comp (ref "R68")
      (value "20R")
      (footprint "eagle-import:R0603")
      (libsource (lib "eagle-import") (part "R-EU_R0603"))
    )
    (comp (ref "R69")
      (value "75R")
      (footprint "eagle-import:R0603")
      (libsource (lib "eagle-import") (part "R-EU_R0603"))
    )
    (comp (ref "SJ1")
      (value "SJ")
      (footprint "eagle-import:SJ")
      (libsource (lib "eagle-import") (part "jumper_252_SJ"))
    )
    (comp (ref "X3")
      (value "F25HP")
      (footprint "eagle-import:F25HP")
      (libsource (lib "eagle-import") (part "F25HP"))
    )
    (comp (ref "X4")
      (value "F15HDH")
      (footprint "eagle-import:HDF15H")
      (libsource (lib "eagle-import") (part "F15HDH"))
    )
  )
  (nets
    (net (code "1") (name "+8V") (class "Default")
      (node (ref "C19") (pin "2") (pinfunction "2_2") (pintype "passive"))
      (node (ref "C43") (pin "1") (pinfunction "1_1") (pintype "passive"))
      (node (ref "C44") (pin "2") (pinfunction "2_2") (pintype "passive"))
      (node (ref "C45") (pin "1") (pinfunction "1_1") (pintype "passive"))
      (node (ref "D7") (pin "C") (pinfunction "C_C") (pintype "passive"))
      (node (ref "IC12") (pin "3") (pinfunction "VI_3") (pintype "input"))
      (node (ref "IC5") (pin "2") (pinfunction "VIN_2") (pintype "power_in"))
      (node (ref "R63") (pin "1") (pinfunction "1_1") (pintype "passive"))
    )
    (net (code "2") (name "-8V") (class "Default")
      (node (ref "C49") (pin "2") (pinfunction "2_2") (pintype "passive"))
      (node (ref "C51") (pin "1") (pinfunction "1_1") (pintype "passive"))
      (node (ref "C52") (pin "2") (pinfunction "2_2") (pintype "passive"))
      (node (ref "D10") (pin "A") (pinfunction "A_A") (pintype "passive"))
      (node (ref "IC13") (pin "2") (pinfunction "VI_2") (pintype "input"))
      (node (ref "IC13") (pin "2@1") (pinfunction "VIN_2@1") (pintype "input"))
      (node (ref "R66") (pin "2") (pinfunction "2_2") (pintype "passive"))
    )
    (net (code "3") (name "1V2") (class "Default")
      (node (ref "C56") (pin "1") (pinfunction "1_1") (pintype "passive"))
      (node (ref "C61") (pin "1") (pinfunction "1_1") (pintype "passive"))
      (node (ref "C62") (pin "1") (pinfunction "1_1") (pintype "passive"))
      (node (ref "C65") (pin "1") (pinfunction "1_1") (pintype "passive"))
      (node (ref "C66") (pin "1") (pinfunction "1_1") (pintype "passive"))
      (node (ref "C69") (pin "1") (pinfunction "1_1") (pintype "passive"))
      (node (ref "IC15") (pin "4") (pinfunction "FB_4") (pintype "passive"))
      (node (ref "IC8") (pin "P128") (pinfunction "VCCINT_P128") (pintype "input"))
      (node (ref "IC8") (pin "P19") (pinfunction "VCCINT_P19") (pintype "input"))
      (node (ref "IC8") (pin "P28") (pinfunction "VCCINT_P28") (pintype "input"))
      (node (ref "IC8") (pin "P52") (pinfunction "VCCINT_P52") (pintype "input"))
      (node (ref "IC8") (pin "P89") (pinfunction "VCCINT_P89") (pintype "input"))
      (node (ref "L3") (pin "2") (pinfunction "2_2") (pintype "passive"))
    )
    (net (code "4") (name "2.5V_A") (class "Default")
      (node (ref "C14") (pin "2") (pinfunction "2_2") (pintype "passive"))
      (node (ref "C22") (pin "2") (pinfunction "2_2") (pintype "passive"))
      (node (ref "C27") (pin "1") (pinfunction "1_1") (pintype "passive"))
      (node (ref "IC4") (pin "2") (pinfunction "VDD_2") (pintype "power_in"))
      (node (ref "IC4") (pin "7") (pinfunction "VDD_7") (pintype "power_in"))
      (node (ref "IC6") (pin "5") (pinfunction "OUT_5") (pintype "passive"))
    )
    (net (code "5") (name "3V3") (class "Default")
      (node (ref "C13") (pin "2") (pinfunction "2_2") (pintype "passive"))
      (node (ref "C21") (pin "2") (pinfunction "2_2") (pintype "passive"))
      (node (ref "C35") (pin "2") (pinfunction "2_2") (pintype "passive"))
      (node (ref "C38") (pin "2") (pinfunction "2_2") (pintype "passive"))
      (node (ref "C39") (pin "1") (pinfunction "1_1") (pintype "passive"))
      (node (ref "C42") (pin "2") (pinfunction "2_2") (pintype "passive"))
      (node (ref "C54") (pin "1") (pinfunction "1_1") (pintype "passive"))
      (node (ref "C57") (pin "1") (pinfunction "1_1") (pintype "passive"))
      (node (ref "C58") (pin "1") (pinfunction "1_1") (pintype "passive"))
      (node (ref "C59") (pin "1") (pinfunction "1_1") (pintype "passive"))
      (node (ref "C60") (pin "1") (pinfunction "1_1") (pintype "passive"))
      (node (ref "C63") (pin "1") (pinfunction "1_1") (pintype "passive"))
      (node (ref "C64") (pin "1") (pinfunction "1_1") (pintype "passive"))
      (node (ref "C67") (pin "1") (pinfunction "1_1") (pintype "passive"))
      (node (ref "C68") (pin "1") (pinfunction "1_1") (pintype "passive"))
      (node (ref "C70") (pin "1") (pinfunction "1_1") (pintype "passive"))
      (node (ref "C71") (pin "1") (pinfunction "1_1") (pintype "passive"))
      (node (ref "C72") (pin "1") (pinfunction "1_1") (pintype "passive"))
      (node (ref "C73") (pin "1") (pinfunction "1_1") (pintype "passive"))
      (node (ref "C74") (pin "1") (pinfunction "1_1") (pintype "passive"))
      (node (ref "C75") (pin "1") (pinfunction "1_1") (pintype "passive"))
      (node (ref "C76") (pin "2") (pinfunction "2_2") (pintype "passive"))
      (node (ref "C77") (pin "1") (pinfunction "1_1") (pintype "passive"))
      (node (ref "C78") (pin "1") (pinfunction "1_1") (pintype "passive"))
      (node (ref "FB1") (pin "1") (pinfunction "1_1") (pintype "passive"))
      (node (ref "FB2") (pin "1") (pinfunction "1_1") (pintype "passive"))
      (node (ref "IC1") (pin "6") (pinfunction "VCC_6") (pintype "power_in"))
      (node (ref "IC11") (pin "3") (pinfunction "~{W}_3") (pintype "bidirectional"))
      (node (ref "IC11") (pin "7") (pinfunction "~{HOLD}_7") (pintype "bidirectional"))
      (node (ref "IC11") (pin "8") (pinfunction "VCC_8") (pintype "bidirectional"))
      (node (ref "IC14") (pin "4") (pinfunction "FB_4") (pintype "passive"))
      (node (ref "IC19") (pin "5") (pinfunction "V+_5") (pintype "power_in"))
      (node (ref "IC2") (pin "20") (pinfunction "VCCIO0_20") (pintype "power_in"))
      (node (ref "IC2") (pin "31") (pinfunction "VCCIO1_31") (pintype "power_in"))
      (node (ref "IC2") (pin "42") (pinfunction "VCCIO2_42") (pintype "power_in"))
      (node (ref "IC2") (pin "50") (pinfunction "VREGIN_50") (pintype "power_in"))
      (node (ref "IC2") (pin "56") (pinfunction "VCCIO3_56") (pintype "power_in"))
      (node (ref "IC20") (pin "11") (pinfunction "+3V_11") (pintype "power_in"))
      (node (ref "IC20") (pin "33") (pinfunction "+3V_33") (pintype "power_in"))
      (node (ref "IC4") (pin "14") (pinfunction "SDI_14") (pintype "input"))
      (node (ref "IC4") (pin "15") (pinfunction "VIO_15") (pintype "power_in"))
      (node (ref "IC4") (pin "19") (pinfunction "SDI_19") (pintype "input"))
      (node (ref "IC4") (pin "20") (pinfunction "VIO_20") (pintype "power_in"))
      (node (ref "IC8") (pin "P103") (pinfunction "VCCO_1_P103") (pintype "input"))
      (node (ref "IC8") (pin "P122") (pinfunction "VCCO_0_P122") (pintype "input"))
      (node (ref "IC8") (pin "P125") (pinfunction "VCCO_0_P125") (pintype "input"))
      (node (ref "IC8") (pin "P129") (pinfunction "VCCAUX_P129") (pintype "input"))
      (node (ref "IC8") (pin "P135") (pinfunction "VCCO_0_P135") (pintype "input"))
      (node (ref "IC8") (pin "P18") (pinfunction "VCCO_3_P18") (pintype "input"))
      (node (ref "IC8") (pin "P20") (pinfunction "VCCAUX_P20") (pintype "input"))
      (node (ref "IC8") (pin "P31") (pinfunction "VCCO_3_P31") (pintype "input"))
      (node (ref "IC8") (pin "P36") (pinfunction "VCCAUX_P36") (pintype "input"))
      (node (ref "IC8") (pin "P4") (pinfunction "VCCO_3_P4") (pintype "input"))
      (node (ref "IC8") (pin "P42") (pinfunction "VCCO_2_P42") (pintype "input"))
      (node (ref "IC8") (pin "P53") (pinfunction "VCCAUX_P53") (pintype "input"))
      (node (ref "IC8") (pin "P63") (pinfunction "VCCO_2_P63") (pintype "input"))
      (node (ref "IC8") (pin "P76") (pinfunction "VCCO_1_P76") (pintype "input"))
      (node (ref "IC8") (pin "P86") (pinfunction "VCCO_1_P86") (pintype "input"))
      (node (ref "IC8") (pin "P90") (pinfunction "VCCAUX_P90") (pintype "input"))
      (node (ref "IC9") (pin "14") (pinfunction "DVCC_14") (pintype "power_in"))
      (node (ref "IC9") (pin "5") (pinfunction "BIN/~{2SCOMP}_5") (pintype "input"))
      (node (ref "JMP1") (pin "3") (pinfunction "3_3") (pintype "passive"))
      (node (ref "JMP2") (pin "3") (pinfunction "3_3") (pintype "passive"))
      (node (ref "JMP3") (pin "3") (pinfunction "3_3") (pintype "passive"))
      (node (ref "L2") (pin "2") (pinfunction "2_2") (pintype "passive"))
      (node (ref "R1") (pin "2") (pinfunction "2_2") (pintype "passive"))
      (node (ref "R15") (pin "2") (pinfunction "2_2") (pintype "passive"))
      (node (ref "R17") (pin "2") (pinfunction "2_2") (pintype "passive"))
      (node (ref "R23") (pin "2") (pinfunction "2_2") (pintype "passive"))
      (node (ref "R4") (pin "2") (pinfunction "2_2") (pintype "passive"))
      (node (ref "R44") (pin "1") (pinfunction "1_1") (pintype "passive"))
      (node (ref "R48") (pin "1") (pinfunction "1_1") (pintype "passive"))
      (node (ref "R5") (pin "2") (pinfunction "2_2") (pintype "passive"))
      (node (ref "R53") (pin "1") (pinfunction "1_1") (pintype "passive"))
      (node (ref "R54") (pin "1") (pinfunction "1_1") (pintype "passive"))
      (node (ref "R60") (pin "2") (pinfunction "2_2") (pintype "passive"))
      (node (ref "R62") (pin "2") (pinfunction "2_2") (pintype "passive"))
      (node (ref "R7") (pin "1") (pinfunction "1_1") (pintype "passive"))
      (node (ref "R8") (pin "1") (pinfunction "1_1") (pintype "passive"))
      (node (ref "X5") (pin "1") (pinfunction "TRI_1") (pintype "input"))
      (node (ref "X5") (pin "4") (pinfunction "VDD_4") (pintype "power_in"))
    )
    (net (code "6") (name "5V") (class "Default")
      (node (ref "C53") (pin "1") (pinfunction "1_1") (pintype "passive"))
      (node (ref "C55") (pin "1") (pinfunction "1_1") (pintype "passive"))
      (node (ref "D3") (pin "C") (pinfunction "C_C") (pintype "passive"))
      (node (ref "IC14") (pin "1") (pinfunction "VIN_1") (pintype "input"))
      (node (ref "IC14") (pin "3") (pinfunction "EN_3") (pintype "passive"))
      (node (ref "IC15") (pin "1") (pinfunction "VIN_1") (pintype "input"))
      (node (ref "IC15") (pin "3") (pinfunction "EN_3") (pintype "passive"))
      (node (ref "Q3") (pin "2") (pinfunction "S_2") (pintype "passive"))
      (node (ref "R21") (pin "2") (pinfunction "2_2") (pintype "passive"))
      (node (ref "R61") (pin "2") (pinfunction "2_2") (pintype "passive"))
    )
    (net (code "7") (name "5V_SWITCHED") (class "Default")
      (node (ref "C47") (pin "1") (pinfunction "1_1") (pintype "passive"))
      (node (ref "IC16") (pin "2") (pinfunction "~{SHDN1}_2") (pintype "power_in"))
      (node (ref "IC16") (pin "4") (pinfunction "~{SHDN2}_4") (pintype "power_in"))
      (node (ref "IC16") (pin "8") (pinfunction "VIN_8") (pintype "power_in"))
      (node (ref "L1") (pin "1") (pinfunction "1_1") (pintype "passive"))
      (node (ref "L5") (pin "1") (pinfunction "1_1") (pintype "passive"))
      (node (ref "Q3") (pin "3") (pinfunction "D_3") (pintype "passive"))
    )
    (net (code "8") (name "ADC1_SDO") (class "Default")
      (node (ref "IC4") (pin "17") (pinfunction "SDO_17") (pintype "output"))
      (node (ref "IC8") (pin "P100") (pinfunction "IO_L33P_1_P100") (pintype "bidirectional"))
      (node (ref "R23") (pin "1") (pinfunction "1_1") (pintype "passive"))
    )
    (net (code "9") (name "ADC2_SDO") (class "Default")
      (node (ref "IC4") (pin "12") (pinfunction "SDO_12") (pintype "output"))
      (node (ref "IC8") (pin "P102") (pinfunction "IO_L32P_1_P102") (pintype "bidirectional"))
      (node (ref "R15") (pin "1") (pinfunction "1_1") (pintype "passive"))
    )
    (net (code "10") (name "ADC_CNV") (class "Default")
      (node (ref "IC4") (pin "11") (pinfunction "CNV_11") (pintype "input"))
      (node (ref "IC4") (pin "16") (pinfunction "CNV_16") (pintype "input"))
      (node (ref "IC8") (pin "P101") (pinfunction "IO_L32N_1_P101") (pintype "bidirectional"))
    )
    (net (code "11") (name "ADC_OFFSET_1") (class "Default")
      (node (ref "C10") (pin "2") (pinfunction "2_2") (pintype "passive"))
      (node (ref "C28") (pin "2") (pinfunction "2_2") (pintype "passive"))
      (node (ref "IC3") (pin "2") (pinfunction "REF_2") (pintype "input"))
      (node (ref "IC7") (pin "2") (pinfunction "REF_2") (pintype "input"))
      (node (ref "R22") (pin "2") (pinfunction "2_2") (pintype "passive"))
      (node (ref "R24") (pin "1") (pinfunction "1_1") (pintype "passive"))
    )
    (net (code "12") (name "ADC_OFFSET_2") (class "Default")
      (node (ref "C18") (pin "2") (pinfunction "2_2") (pintype "passive"))
      (node (ref "C34") (pin "2") (pinfunction "2_2") (pintype "passive"))
      (node (ref "IC3") (pin "8") (pinfunction "IN_8") (pintype "input"))
      (node (ref "IC7") (pin "8") (pinfunction "IN_8") (pintype "input"))
      (node (ref "R19") (pin "1") (pinfunction "1_1") (pintype "passive"))
      (node (ref "R20") (pin "2") (pinfunction "2_2") (pintype "passive"))
    )
    (net (code "13") (name "ADC_REF") (class "Default")
      (node (ref "C20") (pin "2") (pinfunction "2_2") (pintype "passive"))
      (node (ref "C23") (pin "1") (pinfunction "1_1") (pintype "passive"))
      (node (ref "C25") (pin "2") (pinfunction "2_2") (pintype "passive"))
      (node (ref "C26") (pin "2") (pinfunction "2_2") (pintype "passive"))
      (node (ref "IC4") (pin "1") (pinfunction "REF_1") (pintype "input"))
      (node (ref "IC4") (pin "6") (pinfunction "REF_6") (pintype "input"))
      (node (ref "IC5") (pin "6") (pinfunction "VOUT_6") (pintype "output"))
      (node (ref "R19") (pin "2") (pinfunction "2_2") (pintype "passive"))
      (node (ref "R24") (pin "2") (pinfunction "2_2") (pintype "passive"))
    )
    (net (code "14") (name "ADC_SCK") (class "Default")
      (node (ref "IC4") (pin "13") (pinfunction "SCK_13") (pintype "input"))
      (node (ref "IC4") (pin "18") (pinfunction "SCK_18") (pintype "input"))
      (node (ref "IC8") (pin "P99") (pinfunction "IO_L33N_1_P99") (pintype "bidirectional"))
    )
    (net (code "15") (name "AGND") (class "Default")
      (node (ref "C10") (pin "1") (pinfunction "1_1") (pintype "passive"))
      (node (ref "C12") (pin "2") (pinfunction "2_2") (pintype "passive"))
      (node (ref "C14") (pin "1") (pinfunction "1_1") (pintype "passive"))
      (node (ref "C17") (pin "1") (pinfunction "1_1") (pintype "passive"))
      (node (ref "C18") (pin "1") (pinfunction "1_1") (pintype "passive"))
      (node (ref "C19") (pin "1") (pinfunction "1_1") (pintype "passive"))
      (node (ref "C20") (pin "1") (pinfunction "1_1") (pintype "passive"))
      (node (ref "C22") (pin "1") (pinfunction "1_1") (pintype "passive"))
      (node (ref "C23") (pin "2") (pinfunction "2_2") (pintype "passive"))
      (node (ref "C24") (pin "1") (pinfunction "1_1") (pintype "passive"))
      (node (ref "C25") (pin "1") (pinfunction "1_1") (pintype "passive"))
      (node (ref "C27") (pin "2") (pinfunction "2_2") (pintype "passive"))
      (node (ref "C28") (pin "1") (pinfunction "1_1") (pintype "passive"))
      (node (ref "C29") (pin "2") (pinfunction "2_2") (pintype "passive"))
      (node (ref "C30") (pin "2") (pinfunction "2_2") (pintype "passive"))
      (node (ref "C32") (pin "2") (pinfunction "2_2") (pintype "passive"))
      (node (ref "C33") (pin "1") (pinfunction "1_1") (pintype "passive"))
      (node (ref "C34") (pin "1") (pinfunction "1_1") (pintype "passive"))
      (node (ref "C36") (pin "1") (pinfunction "1_1") (pintype "passive"))
      (node (ref "C37") (pin "1") (pinfunction "1_1") (pintype "passive"))
      (node (ref "C40") (pin "1") (pinfunction "1_1") (pintype "passive"))
      (node (ref "C41") (pin "1") (pinfunction "1_1") (pintype "passive"))
      (node (ref "C43") (pin "2") (pinfunction "2_2") (pintype "passive"))
      (node (ref "C46") (pin "2") (pinfunction "2_2") (pintype "passive"))
      (node (ref "C48") (pin "1") (pinfunction "1_1") (pintype "passive"))
      (node (ref "C52") (pin "1") (pinfunction "1_1") (pintype "passive"))
      (node (ref "D2") (pin "A") (pinfunction "A_A") (pintype "passive"))
      (node (ref "D4") (pin "A") (pinfunction "A_A") (pintype "passive"))
      (node (ref "D5") (pin "A") (pinfunction "A_A") (pintype "passive"))
      (node (ref "D6") (pin "A") (pinfunction "A_A") (pintype "passive"))
      (node (ref "D8") (pin "A") (pinfunction "A_A") (pintype "passive"))
      (node (ref "D9") (pin "C") (pinfunction "C_C") (pintype "passive"))
      (node (ref "IC10") (pin "4") (pinfunction "GND_4") (pintype "passive"))
      (node (ref "IC12") (pin "2") (pinfunction "GND_2") (pintype "passive"))
      (node (ref "IC12") (pin "2@1") (pinfunction "GND_2@1") (pintype "passive"))
      (node (ref "IC13") (pin "1") (pinfunction "GND_1") (pintype "passive"))
      (node (ref "IC4") (pin "10") (pinfunction "GND_10") (pintype "passive"))
      (node (ref "IC4") (pin "5") (pinfunction "GND_5") (pintype "passive"))
      (node (ref "IC5") (pin "4") (pinfunction "GND_4") (pintype "passive"))
      (node (ref "IC6") (pin "2") (pinfunction "GND_2") (pintype "power_in"))
      (node (ref "IC9") (pin "18") (pinfunction "DAC_GND_18") (pintype "passive"))
      (node (ref "IC9") (pin "19") (pinfunction "DAC_GND_19") (pintype "passive"))
      (node (ref "IC9") (pin "20") (pinfunction "SIG_GND_20") (pintype "passive"))
      (node (ref "IC9") (pin "21") (pinfunction "SIG_GND_21") (pintype "passive"))
      (node (ref "L4") (pin "1") (pinfunction "1_1") (pintype "passive"))
      (node (ref "Q1") (pin "2") (pinfunction "S_2") (pintype "passive"))
      (node (ref "R20") (pin "1") (pinfunction "1_1") (pintype "passive"))
      (node (ref "R22") (pin "1") (pinfunction "1_1") (pintype "passive"))
      (node (ref "R32") (pin "2") (pinfunction "2_2") (pintype "passive"))
      (node (ref "X3") (pin "1") (pinfunction "1_1") (pintype "passive"))
      (node (ref "X3") (pin "12") (pinfunction "12_12") (pintype "passive"))
      (node (ref "X3") (pin "9") (pinfunction "9_9") (pintype "passive"))
    )
    (net (code "16") (name "ANALOG_SUPPLY_ON") (class "Default")
      (node (ref "Q2") (pin "1") (pinfunction "G_1") (pintype "passive"))
      (node (ref "R67") (pin "1") (pinfunction "1_1") (pintype "passive"))
    )
    (net (code "17") (name "AVDD") (class "Default")
      (node (ref "C30") (pin "1") (pinfunction "1_1") (pintype "passive"))
      (node (ref "C40") (pin "2") (pinfunction "2_2") (pintype "passive"))
      (node (ref "C41") (pin "2") (pinfunction "2_2") (pintype "passive"))
      (node (ref "C46") (pin "1") (pinfunction "1_1") (pintype "passive"))
      (node (ref "D8") (pin "C") (pinfunction "C_C") (pintype "passive"))
      (node (ref "IC10") (pin "2") (pinfunction "VS_2") (pintype "power_in"))
      (node (ref "IC10") (pin "3") (pinfunction "~{SLEEP}_3") (pintype "input"))
      (node (ref "IC12") (pin "1") (pinfunction "VO_1") (pintype "passive"))
      (node (ref "IC17") (pin "5") (pinfunction "V+_5") (pintype "power_in"))
      (node (ref "IC18") (pin "5") (pinfunction "V+_5") (pintype "power_in"))
      (node (ref "IC3") (pin "3") (pinfunction "V+_3") (pintype "power_in"))
      (node (ref "IC6") (pin "1") (pinfunction "IN_1") (pintype "input"))
      (node (ref "IC6") (pin "3") (pinfunction "EN_3") (pintype "input"))
      (node (ref "IC7") (pin "3") (pinfunction "V+_3") (pintype "power_in"))
      (node (ref "IC9") (pin "24") (pinfunction "AVDD_24") (pintype "power_in"))
    )
    (net (code "18") (name "AVSS") (class "Default")
      (node (ref "C48") (pin "2") (pinfunction "2_2") (pintype "passive"))
      (node (ref "D9") (pin "A") (pinfunction "A_A") (pintype "passive"))
      (node (ref "IC13") (pin "3") (pinfunction "VO_3") (pintype "passive"))
      (node (ref "IC17") (pin "2") (pinfunction "V-_2") (pintype "power_in"))
      (node (ref "IC18") (pin "2") (pinfunction "V-_2") (pintype "power_in"))
      (node (ref "IC3") (pin "6") (pinfunction "V-_6") (pintype "power_in"))
      (node (ref "IC7") (pin "6") (pinfunction "V-_6") (pintype "power_in"))
      (node (ref "IC9") (pin "1") (pinfunction "AVSS_1") (pintype "power_in"))
      (node (ref "IC9") (pin "25") (pinfunction "EP_25") (pintype "power_in"))
    )
    (net (code "19") (name "BTN1") (class "Default")
      (node (ref "BTN1") (pin "3") (pinfunction "S_3") (pintype "passive"))
      (node (ref "BTN1") (pin "4") (pinfunction "S_4") (pintype "passive"))
      (node (ref "IC8") (pin "P58") (pinfunction "IO_L14P_D11_2_P58") (pintype "bidirectional"))
      (node (ref "R7") (pin "2") (pinfunction "2_2") (pintype "passive"))
    )
    (net (code "20") (name "BTN2") (class "Default")
      (node (ref "BTN2") (pin "3") (pinfunction "S_3") (pintype "passive"))
      (node (ref "BTN2") (pin "4") (pinfunction "S_4") (pintype "passive"))
      (node (ref "IC8") (pin "P59") (pinfunction "IO_L13N_D10_2_P59") (pintype "bidirectional"))
      (node (ref "R8") (pin "2") (pinfunction "2_2") (pintype "passive"))
    )
    (net (code "21") (name "DAC_REF") (class "Default")
      (node (ref "C36") (pin "2") (pinfunction "2_2") (pintype "passive"))
      (node (ref "C37") (pin "2") (pinfunction "2_2") (pintype "passive"))
      (node (ref "IC10") (pin "6") (pinfunction "OUTPUT_6") (pintype "output"))
      (node (ref "IC9") (pin "17") (pinfunction "REFIN_17") (pintype "bidirectional"))
    )
    (net (code "22") (name "DAC_SCK") (class "Default")
      (node (ref "IC8") (pin "P81") (pinfunction "IO_L46P_1_P81") (pintype "bidirectional"))
      (node (ref "IC9") (pin "8") (pinfunction "SCLK_8") (pintype "input"))
    )
    (net (code "23") (name "DAC_SDI") (class "Default")
      (node (ref "IC8") (pin "P80") (pinfunction "IO_L46N_1_P80") (pintype "bidirectional"))
      (node (ref "IC9") (pin "9") (pinfunction "SDIN_9") (pintype "input"))
    )
    (net (code "24") (name "DAC_SDO") (class "Default")
      (node (ref "IC8") (pin "P75") (pinfunction "IO_L74P_AWAKE_1_P75") (pintype "bidirectional"))
      (node (ref "IC9") (pin "16") (pinfunction "SDO_16") (pintype "output"))
    )
    (net (code "25") (name "DAC_~{CLEAR}") (class "Default")
      (node (ref "IC8") (pin "P78") (pinfunction "IO_L47N_1_P78") (pintype "bidirectional"))
      (node (ref "IC9") (pin "11") (pinfunction "~{CLR}_11") (pintype "input"))
    )
    (net (code "26") (name "DAC_~{LDAC}") (class "Default")
      (node (ref "IC8") (pin "P79") (pinfunction "IO_L47P_1_P79") (pintype "bidirectional"))
      (node (ref "IC9") (pin "10") (pinfunction "~{LDAC}_10") (pintype "input"))
    )
    (net (code "27") (name "DAC_~{SYNC}") (class "Default")
      (node (ref "IC8") (pin "P82") (pinfunction "IO_L45N_1_P82") (pintype "bidirectional"))
      (node (ref "IC9") (pin "7") (pinfunction "~{SYNC}_7") (pintype "input"))
    )
    (net (code "28") (name "DBG_0") (class "Default")
      (node (ref "IC8") (pin "P87") (pinfunction "IO_L42N_GCLK6_TRDY1_1_P87") (pintype "bidirectional"))
      (node (ref "JP2") (pin "1") (pinfunction "1_1") (pintype "passive"))
    )
    (net (code "29") (name "DBG_1") (class "Default")
      (node (ref "IC8") (pin "P88") (pinfunction "IO_L42P_GCLK7_1_P88") (pintype "bidirectional"))
      (node (ref "JP2") (pin "3") (pinfunction "3_3") (pintype "passive"))
    )
    (net (code "30") (name "DBG_2") (class "Default")
      (node (ref "IC8") (pin "P92") (pinfunction "IO_L41N_GCLK8_1_P92") (pintype "bidirectional"))
      (node (ref "JP2") (pin "5") (pinfunction "5_5") (pintype "passive"))
    )
    (net (code "31") (name "DBG_3") (class "Default")
      (node (ref "IC8") (pin "P85") (pinfunction "IO_L43P_GCLK5_1_P85") (pintype "bidirectional"))
      (node (ref "JP2") (pin "2") (pinfunction "2_2") (pintype "passive"))
      (node (ref "JP3") (pin "1") (pinfunction "1_1") (pintype "passive"))
    )
    (net (code "32") (name "DBG_4") (class "Default")
      (node (ref "IC8") (pin "P97") (pinfunction "IO_L34N_1_P97") (pintype "bidirectional"))
      (node (ref "JP2") (pin "4") (pinfunction "4_4") (pintype "passive"))
      (node (ref "JP3") (pin "3") (pinfunction "3_3") (pintype "passive"))
    )
    (net (code "33") (name "DBG_5") (class "Default")
      (node (ref "IC8") (pin "P98") (pinfunction "IO_L34P_1_P98") (pintype "bidirectional"))
      (node (ref "JP2") (pin "6") (pinfunction "6_6") (pintype "passive"))
      (node (ref "JP3") (pin "5") (pinfunction "5_5") (pintype "passive"))
    )
    (net (code "34") (name "DBG_6") (class "Default")
      (node (ref "IC8") (pin "P95") (pinfunction "IO_L40P_GCLK11_1_P95") (pintype "bidirectional"))
      (node (ref "JP3") (pin "2") (pinfunction "2_2") (pintype "passive"))
    )
    (net (code "35") (name "DBG_7") (class "Default")
      (node (ref "IC8") (pin "P94") (pinfunction "IO_L40N_GCLK10_1_P94") (pintype "bidirectional"))
      (node (ref "JP3") (pin "4") (pinfunction "4_4") (pintype "passive"))
    )
    (net (code "36") (name "DONE") (class "Default")
      (node (ref "IC8") (pin "P71") (pinfunction "DONE_2_P71") (pintype "bidirectional"))
      (node (ref "LED2") (pin "A") (pinfunction "A_A") (pintype "passive"))
      (node (ref "R44") (pin "2") (pinfunction "2_2") (pintype "passive"))
    )
    (net (code "37") (name "FIFO_CLKOUT") (class "Default")
      (node (ref "IC2") (pin "32") (pinfunction "ACBUS5_32") (pintype "bidirectional"))
      (node (ref "IC8") (pin "P133") (pinfunction "IO_L34N_GCLK18_0_P133") (pintype "bidirectional"))
    )
    (net (code "38") (name "FIFO_D0") (class "Default")
      (node (ref "IC2") (pin "16") (pinfunction "ADBUS0_16") (pintype "bidirectional"))
      (node (ref "IC8") (pin "P132") (pinfunction "IO_L35P_GCLK17_0_P132") (pintype "bidirectional"))
    )
    (net (code "39") (name "FIFO_D1") (class "Default")
      (node (ref "IC2") (pin "17") (pinfunction "ADBUS1_17") (pintype "bidirectional"))
      (node (ref "IC8") (pin "P131") (pinfunction "IO_L35N_GCLK16_0_P131") (pintype "bidirectional"))
    )
    (net (code "40") (name "FIFO_D2") (class "Default")
      (node (ref "IC2") (pin "18") (pinfunction "ADBUS2_18") (pintype "bidirectional"))
      (node (ref "IC8") (pin "P127") (pinfunction "IO_L36P_GCLK15_0_P127") (pintype "bidirectional"))
    )
    (net (code "41") (name "FIFO_D3") (class "Default")
      (node (ref "IC2") (pin "19") (pinfunction "ADBUS3_19") (pintype "bidirectional"))
      (node (ref "IC8") (pin "P126") (pinfunction "IO_L36N_GCLK14_0_P126") (pintype "bidirectional"))
    )
    (net (code "42") (name "FIFO_D4") (class "Default")
      (node (ref "IC2") (pin "21") (pinfunction "ADBUS4_21") (pintype "bidirectional"))
      (node (ref "IC8") (pin "P124") (pinfunction "IO_L37P_GCLK13_0_P124") (pintype "bidirectional"))
    )
    (net (code "43") (name "FIFO_D5") (class "Default")
      (node (ref "IC2") (pin "22") (pinfunction "ADBUS5_22") (pintype "bidirectional"))
      (node (ref "IC8") (pin "P123") (pinfunction "IO_L37N_GCLK12_0_P123") (pintype "bidirectional"))
    )
    (net (code "44") (name "FIFO_D6") (class "Default")
      (node (ref "IC2") (pin "23") (pinfunction "ADBUS6_23") (pintype "bidirectional"))
      (node (ref "IC8") (pin "P121") (pinfunction "IO_L62P_0_P121") (pintype "bidirectional"))
    )
    (net (code "45") (name "FIFO_D7") (class "Default")
      (node (ref "IC2") (pin "24") (pinfunction "ADBUS7_24") (pintype "bidirectional"))
      (node (ref "IC8") (pin "P120") (pinfunction "IO_L62N_VREF_0_P120") (pintype "bidirectional"))
    )
    (net (code "46") (name "FIFO_SIWUB") (class "Default")
      (node (ref "IC2") (pin "30") (pinfunction "ACBUS4_30") (pintype "bidirectional"))
      (node (ref "IC8") (pin "P115") (pinfunction "IO_L65P_SCP3_0_P115") (pintype "bidirectional"))
    )
    (net (code "47") (name "FIFO_~{OE}") (class "Default")
      (node (ref "IC2") (pin "33") (pinfunction "ACBUS6_33") (pintype "bidirectional"))
      (node (ref "IC8") (pin "P114") (pinfunction "IO_L65N_SCP2_0_P114") (pintype "bidirectional"))
    )
    (net (code "48") (name "FIFO_~{RD}") (class "Default")
      (node (ref "IC2") (pin "28") (pinfunction "ACBUS2_28") (pintype "bidirectional"))
      (node (ref "IC8") (pin "P117") (pinfunction "IO_L64P_SCP5_0_P117") (pintype "bidirectional"))
    )
    (net (code "49") (name "FIFO_~{RXF}") (class "Default")
      (node (ref "IC2") (pin "26") (pinfunction "ACBUS0_26") (pintype "bidirectional"))
      (node (ref "IC8") (pin "P119") (pinfunction "IO_L63P_SCP7_0_P119") (pintype "bidirectional"))
    )
    (net (code "50") (name "FIFO_~{TXE}") (class "Default")
      (node (ref "IC2") (pin "27") (pinfunction "ACBUS1_27") (pintype "bidirectional"))
      (node (ref "IC8") (pin "P118") (pinfunction "IO_L63N_SCP6_0_P118") (pintype "bidirectional"))
    )
    (net (code "51") (name "FIFO_~{WR}") (class "Default")
      (node (ref "IC2") (pin "29") (pinfunction "ACBUS3_29") (pintype "bidirectional"))
      (node (ref "IC8") (pin "P116") (pinfunction "IO_L64N_SCP4_0_P116") (pintype "bidirectional"))
    )
    (net (code "52") (name "FLASH_DQ0{slash}MOSI") (class "Default")
      (node (ref "IC11") (pin "5") (pinfunction "DQ0_5") (pintype "bidirectional"))
      (node (ref "IC8") (pin "P64") (pinfunction "IO_L3N_MOSI_CSI_B_MISO0_2_P64") (pintype "bidirectional"))
    )
    (net (code "53") (name "FLASH_DQ1{slash}MISO") (class "Default")
      (node (ref "IC8") (pin "P65") (pinfunction "IO_L3P_D0_DIN_MISO_MISO1_2_P65") (pintype "bidirectional"))
      (node (ref "R59") (pin "2") (pinfunction "2_2") (pintype "passive"))
    )
    (net (code "54") (name "FLASH_SCK") (class "Default")
      (node (ref "IC11") (pin "6") (pinfunction "C_6") (pintype "bidirectional"))
      (node (ref "IC8") (pin "P70") (pinfunction "IO_L1P_CCLK_2_P70") (pintype "bidirectional"))
      (node (ref "R58") (pin "2") (pinfunction "2_2") (pintype "passive"))
      (node (ref "R60") (pin "1") (pinfunction "1_1") (pintype "passive"))
    )
    (net (code "55") (name "FLASH_~{CS}") (class "Default")
      (node (ref "IC11") (pin "1") (pinfunction "~{S}_1") (pintype "bidirectional"))
      (node (ref "IC8") (pin "P38") (pinfunction "IO_L65N_CSO_B_2_P38") (pintype "bidirectional"))
      (node (ref "R62") (pin "1") (pinfunction "1_1") (pintype "passive"))
    )
    (net (code "56") (name "FT_1V8") (class "Default")
      (node (ref "C1") (pin "1") (pinfunction "1_1") (pintype "passive"))
      (node (ref "C2") (pin "1") (pinfunction "1_1") (pintype "passive"))
      (node (ref "C9") (pin "1") (pinfunction "1_1") (pintype "passive"))
      (node (ref "IC2") (pin "12") (pinfunction "VCORE0_12") (pintype "power_in"))
      (node (ref "IC2") (pin "37") (pinfunction "VCORE1_37") (pintype "power_in"))
      (node (ref "IC2") (pin "49") (pinfunction "VREGOUT_49") (pintype "power_in"))
      (node (ref "IC2") (pin "64") (pinfunction "VCORE2_64") (pintype "power_in"))
    )
    (net (code "57") (name "GND") (class "Default")
      (node (ref "BTN1") (pin "1") (pinfunction "P_1") (pintype "passive"))
      (node (ref "BTN1") (pin "2") (pinfunction "P_2") (pintype "passive"))
      (node (ref "BTN2") (pin "1") (pinfunction "P_1") (pintype "passive"))
      (node (ref "BTN2") (pin "2") (pinfunction "P_2") (pintype "passive"))
      (node (ref "C1") (pin "2") (pinfunction "2_2") (pintype "passive"))
      (node (ref "C11") (pin "2") (pinfunction "2_2") (pintype "passive"))
      (node (ref "C13") (pin "1") (pinfunction "1_1") (pintype "passive"))
      (node (ref "C15") (pin "2") (pinfunction "2_2") (pintype "passive"))
      (node (ref "C2") (pin "2") (pinfunction "2_2") (pintype "passive"))
      (node (ref "C21") (pin "1") (pinfunction "1_1") (pintype "passive"))
      (node (ref "C3") (pin "2") (pinfunction "2_2") (pintype "passive"))
      (node (ref "C35") (pin "1") (pinfunction "1_1") (pintype "passive"))
      (node (ref "C38") (pin "1") (pinfunction "1_1") (pintype "passive"))
      (node (ref "C39") (pin "2") (pinfunction "2_2") (pintype "passive"))
      (node (ref "C4") (pin "1") (pinfunction "1_1") (pintype "passive"))
      (node (ref "C42") (pin "1") (pinfunction "1_1") (pintype "passive"))
      (node (ref "C44") (pin "1") (pinfunction "1_1") (pintype "passive"))
      (node (ref "C47") (pin "2") (pinfunction "2_2") (pintype "passive"))
      (node (ref "C5") (pin "2") (pinfunction "2_2") (pintype "passive"))
      (node (ref "C51") (pin "2") (pinfunction "2_2") (pintype "passive"))
      (node (ref "C53") (pin "2") (pinfunction "2_2") (pintype "passive"))
      (node (ref "C54") (pin "2") (pinfunction "2_2") (pintype "passive"))
      (node (ref "C55") (pin "2") (pinfunction "2_2") (pintype "passive"))
      (node (ref "C56") (pin "2") (pinfunction "2_2") (pintype "passive"))
      (node (ref "C57") (pin "2") (pinfunction "2_2") (pintype "passive"))
      (node (ref "C58") (pin "2") (pinfunction "2_2") (pintype "passive"))
      (node (ref "C59") (pin "2") (pinfunction "2_2") (pintype "passive"))
      (node (ref "C6") (pin "2") (pinfunction "2_2") (pintype "passive"))
      (node (ref "C60") (pin "2") (pinfunction "2_2") (pintype "passive"))
      (node (ref "C61") (pin "2") (pinfunction "2_2") (pintype "passive"))
      (node (ref "C62") (pin "2") (pinfunction "2_2") (pintype "passive"))
      (node (ref "C63") (pin "2") (pinfunction "2_2") (pintype "passive"))
      (node (ref "C64") (pin "2") (pinfunction "2_2") (pintype "passive"))
      (node (ref "C65") (pin "2") (pinfunction "2_2") (pintype "passive"))
      (node (ref "C66") (pin "2") (pinfunction "2_2") (pintype "passive"))
      (node (ref "C67") (pin "2") (pinfunction "2_2") (pintype "passive"))
      (node (ref "C68") (pin "2") (pinfunction "2_2") (pintype "passive"))
      (node (ref "C69") (pin "2") (pinfunction "2_2") (pintype "passive"))
      (node (ref "C7") (pin "2") (pinfunction "2_2") (pintype "passive"))
      (node (ref "C70") (pin "2") (pinfunction "2_2") (pintype "passive"))
      (node (ref "C71") (pin "2") (pinfunction "2_2") (pintype "passive"))
      (node (ref "C72") (pin "2") (pinfunction "2_2") (pintype "passive"))
      (node (ref "C73") (pin "2") (pinfunction "2_2") (pintype "passive"))
      (node (ref "C74") (pin "2") (pinfunction "2_2") (pintype "passive"))
      (node (ref "C75") (pin "2") (pinfunction "2_2") (pintype "passive"))
      (node (ref "C76") (pin "1") (pinfunction "1_1") (pintype "passive"))
      (node (ref "C77") (pin "2") (pinfunction "2_2") (pintype "passive"))
      (node (ref "C78") (pin "2") (pinfunction "2_2") (pintype "passive"))
      (node (ref "C8") (pin "2") (pinfunction "2_2") (pintype "passive"))
      (node (ref "C9") (pin "2") (pinfunction "2_2") (pintype "passive"))
      (node (ref "D1") (pin "1") (pinfunction "GND_1") (pintype "passive"))
      (node (ref "D11") (pin "C") (pinfunction "C_C") (pintype "passive"))
      (node (ref "IC1") (pin "2") (pinfunction "GND_2") (pintype "power_in"))
      (node (ref "IC11") (pin "4") (pinfunction "VSS_4") (pintype "bidirectional"))
      (node (ref "IC14") (pin "2") (pinfunction "GND_2") (pintype "passive"))
      (node (ref "IC15") (pin "2") (pinfunction "GND_2") (pintype "passive"))
      (node (ref "IC16") (pin "3") (pinfunction "GND_3") (pintype "power_in"))
      (node (ref "IC16") (pin "7") (pinfunction "PGND_7") (pintype "power_in"))
      (node (ref "IC16") (pin "9") (pinfunction "PGND_9") (pintype "power_in"))
      (node (ref "IC19") (pin "2") (pinfunction "V-_2") (pintype "power_in"))
      (node (ref "IC2") (pin "1") (pinfunction "GND0_1") (pintype "power_in"))
      (node (ref "IC2") (pin "10") (pinfunction "AGND_10") (pintype "power_in"))
      (node (ref "IC2") (pin "11") (pinfunction "GND2_11") (pintype "power_in"))
      (node (ref "IC2") (pin "13") (pinfunction "TEST_13") (pintype "bidirectional"))
      (node (ref "IC2") (pin "15") (pinfunction "GND3_15") (pintype "power_in"))
      (node (ref "IC2") (pin "25") (pinfunction "GND4_25") (pintype "power_in"))
      (node (ref "IC2") (pin "35") (pinfunction "GND5_35") (pintype "power_in"))
      (node (ref "IC2") (pin "47") (pinfunction "GND6_47") (pintype "power_in"))
      (node (ref "IC2") (pin "5") (pinfunction "GND1_5") (pintype "power_in"))
      (node (ref "IC2") (pin "51") (pinfunction "GND7_51") (pintype "power_in"))
      (node (ref "IC20") (pin "12") (pinfunction "GND_12") (pintype "power_in"))
      (node (ref "IC20") (pin "34") (pinfunction "GND_34") (pintype "power_in"))
      (node (ref "IC8") (pin "P108") (pinfunction "GND_P108") (pintype "power_in"))
      (node (ref "IC8") (pin "P113") (pinfunction "GND_P113") (pintype "power_in"))
      (node (ref "IC8") (pin "P13") (pinfunction "GND_P13") (pintype "power_in"))
      (node (ref "IC8") (pin "P130") (pinfunction "GND_P130") (pintype "power_in"))
      (node (ref "IC8") (pin "P136") (pinfunction "GND_P136") (pintype "power_in"))
      (node (ref "IC8") (pin "P25") (pinfunction "GND_P25") (pintype "power_in"))
      (node (ref "IC8") (pin "P3") (pinfunction "GND_P3") (pintype "power_in"))
      (node (ref "IC8") (pin "P49") (pinfunction "GND_P49") (pintype "power_in"))
      (node (ref "IC8") (pin "P54") (pinfunction "GND_P54") (pintype "power_in"))
      (node (ref "IC8") (pin "P68") (pinfunction "GND_P68") (pintype "power_in"))
      (node (ref "IC8") (pin "P73") (pinfunction "SUSPEND_P73") (pintype "input"))
      (node (ref "IC8") (pin "P77") (pinfunction "GND_P77") (pintype "power_in"))
      (node (ref "IC8") (pin "P91") (pinfunction "GND_P91") (pintype "power_in"))
      (node (ref "IC8") (pin "P96") (pinfunction "GND_P96") (pintype "power_in"))
      (node (ref "IC9") (pin "15") (pinfunction "GND_15") (pintype "passive"))
      (node (ref "JMP1") (pin "1") (pinfunction "1_1") (pintype "passive"))
      (node (ref "JMP2") (pin "1") (pinfunction "1_1") (pintype "passive"))
      (node (ref "JMP3") (pin "1") (pinfunction "1_1") (pintype "passive"))
      (node (ref "JP3") (pin "6") (pinfunction "6_6") (pintype "passive"))
      (node (ref "L4") (pin "2") (pinfunction "2_2") (pintype "passive"))
      (node (ref "LED") (pin "C") (pinfunction "C_C") (pintype "passive"))
      (node (ref "LED1") (pin "C") (pinfunction "C_C") (pintype "passive"))
      (node (ref "LED2") (pin "C") (pinfunction "C_C") (pintype "passive"))
      (node (ref "Q2") (pin "2") (pinfunction "S_2") (pintype "passive"))
      (node (ref "R18") (pin "1") (pinfunction "1_1") (pintype "passive"))
      (node (ref "R2") (pin "1") (pinfunction "1_1") (pintype "passive"))
      (node (ref "R26") (pin "1") (pinfunction "1_1") (pintype "passive"))
      (node (ref "R35") (pin "1") (pinfunction "1_1") (pintype "passive"))
      (node (ref "R58") (pin "1") (pinfunction "1_1") (pintype "passive"))
      (node (ref "R64") (pin "2") (pinfunction "2_2") (pintype "passive"))
      (node (ref "R65") (pin "1") (pinfunction "1_1") (pintype "passive"))
      (node (ref "R9") (pin "2") (pinfunction "2_2") (pintype "passive"))
      (node (ref "RST") (pin "1") (pinfunction "1_1") (pintype "passive"))
      (node (ref "X2") (pin "4") (pinfunction "4_4") (pintype "passive"))
      (node (ref "X4") (pin "10") (pinfunction "10_10") (pintype "passive"))
      (node (ref "X4") (pin "5") (pinfunction "5_5") (pintype "passive"))
      (node (ref "X4") (pin "6") (pinfunction "6_6") (pintype "passive"))
      (node (ref "X4") (pin "7") (pinfunction "7_7") (pintype "passive"))
      (node (ref "X4") (pin "8") (pinfunction "8_8") (pintype "passive"))
      (node (ref "X5") (pin "2") (pinfunction "GND_2") (pintype "power_in"))
    )
    (net (code "58") (name "IO_P39") (class "Default")
      (node (ref "IC8") (pin "P39") (pinfunction "IO_L65P_INIT_B_2_P39") (pintype "bidirectional"))
      (node (ref "R54") (pin "2") (pinfunction "2_2") (pintype "passive"))
    )
    (net (code "59") (name "IO_P60") (class "Default")
      (node (ref "IC8") (pin "P60") (pinfunction "IO_L13P_M1_2_P60") (pintype "bidirectional"))
      (node (ref "JMP2") (pin "2") (pinfunction "2_2") (pintype "passive"))
    )
    (net (code "60") (name "IO_P69") (class "Default")
      (node (ref "IC8") (pin "P69") (pinfunction "IO_L1N_M0_CMPMISO_2_P69") (pintype "bidirectional"))
      (node (ref "JMP3") (pin "2") (pinfunction "2_2") (pintype "passive"))
    )
    (net (code "61") (name "IO_P144") (class "Default")
      (node (ref "IC8") (pin "P144") (pinfunction "IO_L1P_HSWAPEN_0_P144") (pintype "bidirectional"))
      (node (ref "JMP1") (pin "2") (pinfunction "2_2") (pintype "passive"))
    )
    (net (code "62") (name "Net-(C4-Pad2)") (class "Default")
      (node (ref "C4") (pin "2") (pinfunction "2_2") (pintype "passive"))
      (node (ref "X2") (pin "S1") (pinfunction "S1_S1") (pintype "passive"))
    )
    (net (code "63") (name "Net-(C26-Pad1)") (class "Default")
      (node (ref "C26") (pin "1") (pinfunction "1_1") (pintype "passive"))
      (node (ref "R25") (pin "1") (pinfunction "1_1") (pintype "passive"))
    )
    (net (code "64") (name "Net-(C50-Pad2)") (class "Default")
      (node (ref "C50") (pin "2") (pinfunction "2_2") (pintype "passive"))
      (node (ref "D10") (pin "C") (pinfunction "C_C") (pintype "passive"))
      (node (ref "D11") (pin "A") (pinfunction "A_A") (pintype "passive"))
    )
    (net (code "65") (name "Net-(D3-PadA)") (class "Default")
      (node (ref "D3") (pin "A") (pinfunction "A_A") (pintype "passive"))
      (node (ref "F1") (pin "1") (pinfunction "1_1") (pintype "passive"))
      (node (ref "R26") (pin "2") (pinfunction "2_2") (pintype "passive"))
    )
    (net (code "66") (name "Net-(IC1-CLK)") (class "Default")
      (node (ref "IC1") (pin "4") (pinfunction "CLK_4") (pintype "input"))
      (node (ref "IC2") (pin "62") (pinfunction "EECLK_62") (pintype "bidirectional"))
      (node (ref "R1") (pin "1") (pinfunction "1_1") (pintype "passive"))
    )
    (net (code "67") (name "Net-(IC1-CS)") (class "Default")
      (node (ref "IC1") (pin "5") (pinfunction "CS_5") (pintype "input"))
      (node (ref "IC2") (pin "63") (pinfunction "EECS_63") (pintype "bidirectional"))
      (node (ref "R5") (pin "1") (pinfunction "1_1") (pintype "passive"))
    )
    (net (code "68") (name "Net-(IC1-DI)") (class "Default")
      (node (ref "IC1") (pin "3") (pinfunction "DI_3") (pintype "input"))
      (node (ref "IC2") (pin "61") (pinfunction "EEDATA_61") (pintype "bidirectional"))
      (node (ref "R3") (pin "1") (pinfunction "1_1") (pintype "passive"))
    )
    (net (code "69") (name "Net-(IC1-DO)") (class "Default")
      (node (ref "IC1") (pin "1") (pinfunction "DO_1") (pintype "tri_state"))
      (node (ref "R3") (pin "2") (pinfunction "2_2") (pintype "passive"))
      (node (ref "R4") (pin "1") (pinfunction "1_1") (pintype "passive"))
    )
    (net (code "70") (name "Net-(IC2-DM)") (class "Default")
      (node (ref "IC2") (pin "7") (pinfunction "DM_7") (pintype "bidirectional"))
      (node (ref "R10") (pin "2") (pinfunction "2_2") (pintype "passive"))
    )
    (net (code "71") (name "Net-(IC2-DP)") (class "Default")
      (node (ref "IC2") (pin "8") (pinfunction "DP_8") (pintype "bidirectional"))
      (node (ref "R11") (pin "2") (pinfunction "2_2") (pintype "passive"))
    )
    (net (code "72") (name "Net-(IC2-OSCI)") (class "Default")
      (node (ref "C3") (pin "1") (pinfunction "1_1") (pintype "passive"))
      (node (ref "IC2") (pin "2") (pinfunction "OSCI_2") (pintype "input"))
      (node (ref "X1") (pin "3") (pinfunction "2_3") (pintype "passive"))
    )
    (net (code "73") (name "Net-(IC2-OSCO)") (class "Default")
      (node (ref "C6") (pin "1") (pinfunction "1_1") (pintype "passive"))
      (node (ref "IC2") (pin "3") (pinfunction "OSCO_3") (pintype "output"))
      (node (ref "X1") (pin "1") (pinfunction "1_1") (pintype "passive"))
    )
    (net (code "74") (name "Net-(IC2-REF)") (class "Default")
      (node (ref "IC2") (pin "6") (pinfunction "REF_6") (pintype "bidirectional"))
      (node (ref "R9") (pin "1") (pinfunction "1_1") (pintype "passive"))
    )
    (net (code "75") (name "Net-(IC2-RESET#)") (class "Default")
      (node (ref "IC2") (pin "14") (pinfunction "RESET#_14") (pintype "bidirectional"))
      (node (ref "R17") (pin "1") (pinfunction "1_1") (pintype "passive"))
      (node (ref "RST") (pin "2") (pinfunction "2_2") (pintype "passive"))
    )
    (net (code "76") (name "Net-(IC2-VPHY)") (class "Default")
      (node (ref "C5") (pin "1") (pinfunction "1_1") (pintype "passive"))
      (node (ref "C8") (pin "1") (pinfunction "1_1") (pintype "passive"))
      (node (ref "FB1") (pin "2") (pinfunction "2_2") (pintype "passive"))
      (node (ref "IC2") (pin "4") (pinfunction "VPHY_4") (pintype "bidirectional"))
    )
    (net (code "77") (name "Net-(IC2-VPLL)") (class "Default")
      (node (ref "C11") (pin "1") (pinfunction "1_1") (pintype "passive"))
      (node (ref "C15") (pin "1") (pinfunction "1_1") (pintype "passive"))
      (node (ref "FB2") (pin "2") (pinfunction "2_2") (pintype "passive"))
      (node (ref "IC2") (pin "9") (pinfunction "VPLL_9") (pintype "bidirectional"))
    )
    (net (code "78") (name "Net-(IC3-FB)") (class "Default")
      (node (ref "C16") (pin "2") (pinfunction "2_2") (pintype "passive"))
      (node (ref "IC3") (pin "1") (pinfunction "FB_1") (pintype "input"))
      (node (ref "R13") (pin "2") (pinfunction "2_2") (pintype "passive"))
      (node (ref "R14") (pin "1") (pinfunction "1_1") (pintype "passive"))
    )
    (net (code "79") (name "Net-(IC3-OUT+)") (class "Default")
      (node (ref "C16") (pin "1") (pinfunction "1_1") (pintype "passive"))
      (node (ref "IC3") (pin "4") (pinfunction "OUT+_4") (pintype "output"))
      (node (ref "R12") (pin "1") (pinfunction "1_1") (pintype "passive"))
      (node (ref "R13") (pin "1") (pinfunction "1_1") (pintype "passive"))
    )
    (net (code "80") (name "Net-(IC3-OUT-)") (class "Default")
      (node (ref "IC3") (pin "5") (pinfunction "OUT-_5") (pintype "output"))
      (node (ref "R16") (pin "1") (pinfunction "1_1") (pintype "passive"))
    )
    (net (code "81") (name "Net-(IC4A-IN+)") (class "Default")
      (node (ref "C33") (pin "2") (pinfunction "2_2") (pintype "passive"))
      (node (ref "IC4") (pin "3") (pinfunction "IN+_3") (pintype "input"))
      (node (ref "R30") (pin "2") (pinfunction "2_2") (pintype "passive"))
    )
    (net (code "82") (name "Net-(IC4A-IN-)") (class "Default")
      (node (ref "C29") (pin "1") (pinfunction "1_1") (pintype "passive"))
      (node (ref "IC4") (pin "4") (pinfunction "IN-_4") (pintype "input"))
      (node (ref "R27") (pin "2") (pinfunction "2_2") (pintype "passive"))
    )
    (net (code "83") (name "Net-(IC4B-IN+)") (class "Default")
      (node (ref "C17") (pin "2") (pinfunction "2_2") (pintype "passive"))
      (node (ref "IC4") (pin "8") (pinfunction "IN+_8") (pintype "input"))
      (node (ref "R16") (pin "2") (pinfunction "2_2") (pintype "passive"))
    )
    (net (code "84") (name "Net-(IC4B-IN-)") (class "Default")
      (node (ref "C12") (pin "1") (pinfunction "1_1") (pintype "passive"))
      (node (ref "IC4") (pin "9") (pinfunction "IN-_9") (pintype "input"))
      (node (ref "R12") (pin "2") (pinfunction "2_2") (pintype "passive"))
    )
    (net (code "85") (name "Net-(IC5-COMP)") (class "Default")
      (node (ref "IC5") (pin "7") (pinfunction "COMP_7") (pintype "passive"))
      (node (ref "R25") (pin "2") (pinfunction "2_2") (pintype "passive"))
    )
    (net (code "86") (name "Net-(IC5-TRIM)") (class "Default")
      (node (ref "C24") (pin "2") (pinfunction "2_2") (pintype "passive"))
      (node (ref "IC5") (pin "5") (pinfunction "TRIM_5") (pintype "input"))
    )
    (net (code "87") (name "Net-(IC6-NR{slash}FB)") (class "Default")
      (node (ref "C32") (pin "1") (pinfunction "1_1") (pintype "passive"))
      (node (ref "IC6") (pin "4") (pinfunction "NR/FB_4") (pintype "passive"))
    )
    (net (code "88") (name "Net-(IC7-FB)") (class "Default")
      (node (ref "C31") (pin "2") (pinfunction "2_2") (pintype "passive"))
      (node (ref "IC7") (pin "1") (pinfunction "FB_1") (pintype "input"))
      (node (ref "R28") (pin "2") (pinfunction "2_2") (pintype "passive"))
      (node (ref "R29") (pin "1") (pinfunction "1_1") (pintype "passive"))
    )
    (net (code "89") (name "Net-(IC7-OUT+)") (class "Default")
      (node (ref "C31") (pin "1") (pinfunction "1_1") (pintype "passive"))
      (node (ref "IC7") (pin "4") (pinfunction "OUT+_4") (pintype "output"))
      (node (ref "R27") (pin "1") (pinfunction "1_1") (pintype "passive"))
      (node (ref "R28") (pin "1") (pinfunction "1_1") (pintype "passive"))
    )
    (net (code "90") (name "Net-(IC7-OUT-)") (class "Default")
      (node (ref "IC7") (pin "5") (pinfunction "OUT-_5") (pintype "output"))
      (node (ref "R30") (pin "1") (pinfunction "1_1") (pintype "passive"))
    )
    (net (code "91") (name "Net-(IC8B-IO_L41P_GCLK9_IRDY1_1)") (class "Default")
      (node (ref "IC8") (pin "P93") (pinfunction "IO_L41P_GCLK9_IRDY1_1_P93") (pintype "bidirectional"))
      (node (ref "R34") (pin "2") (pinfunction "2_2") (pintype "passive"))
    )
    (net (code "92") (name "Net-(IC8C-CMPCS_B_2)") (class "Default")
      (node (ref "IC8") (pin "P72") (pinfunction "CMPCS_B_2_P72") (pintype "bidirectional"))
      (node (ref "R48") (pin "2") (pinfunction "2_2") (pintype "passive"))
    )
    (net (code "93") (name "Net-(IC8C-IO_L12P_D1_MISO2_2)") (class "Default")
      (node (ref "IC8") (pin "P62") (pinfunction "IO_L12P_D1_MISO2_2_P62") (pintype "bidirectional"))
      (node (ref "R67") (pin "2") (pinfunction "2_2") (pintype "passive"))
    )
    (net (code "94") (name "Net-(IC11-DQ1)") (class "Default")
      (node (ref "IC11") (pin "2") (pinfunction "DQ1_2") (pintype "bidirectional"))
      (node (ref "R59") (pin "1") (pinfunction "1_1") (pintype "passive"))
    )
    (net (code "95") (name "Net-(IC14-SW)") (class "Default")
      (node (ref "IC14") (pin "5") (pinfunction "SW_5") (pintype "output"))
      (node (ref "L2") (pin "1") (pinfunction "1_1") (pintype "passive"))
    )
    (net (code "96") (name "Net-(IC15-SW)") (class "Default")
      (node (ref "IC15") (pin "5") (pinfunction "SW_5") (pintype "output"))
      (node (ref "L3") (pin "1") (pinfunction "1_1") (pintype "passive"))
    )
    (net (code "97") (name "Net-(IC16-FB2)") (class "Default")
      (node (ref "C45") (pin "2") (pinfunction "2_2") (pintype "passive"))
      (node (ref "IC16") (pin "5") (pinfunction "FB2_5") (pintype "power_in"))
      (node (ref "R63") (pin "2") (pinfunction "2_2") (pintype "passive"))
      (node (ref "R64") (pin "1") (pinfunction "1_1") (pintype "passive"))
    )
    (net (code "98") (name "Net-(IC16-NFB1)") (class "Default")
      (node (ref "C49") (pin "1") (pinfunction "1_1") (pintype "passive"))
      (node (ref "IC16") (pin "1") (pinfunction "NFB1_1") (pintype "power_in"))
      (node (ref "R65") (pin "2") (pinfunction "2_2") (pintype "passive"))
      (node (ref "R66") (pin "1") (pinfunction "1_1") (pintype "passive"))
    )
    (net (code "99") (name "Net-(IC16-SW1)") (class "Default")
      (node (ref "C50") (pin "1") (pinfunction "1_1") (pintype "passive"))
      (node (ref "IC16") (pin "10") (pinfunction "SW1_10") (pintype "power_in"))
      (node (ref "L5") (pin "2") (pinfunction "2_2") (pintype "passive"))
    )
    (net (code "100") (name "Net-(IC16-SW2)") (class "Default")
      (node (ref "D7") (pin "A") (pinfunction "A_A") (pintype "passive"))
      (node (ref "IC16") (pin "6") (pinfunction "SW2_6") (pintype "power_in"))
      (node (ref "L1") (pin "2") (pinfunction "2_2") (pintype "passive"))
    )
    (net (code "101") (name "Net-(IC17-+IN)") (class "Default")
      (node (ref "IC17") (pin "3") (pinfunction "+IN_3") (pintype "input"))
      (node (ref "IC9") (pin "3") (pinfunction "VOUTA_3") (pintype "output"))
    )
    (net (code "102") (name "Net-(IC17--IN)") (class "Default")
      (node (ref "IC17") (pin "1") (pinfunction "OUT_1") (pintype "output"))
      (node (ref "IC17") (pin "4") (pinfunction "-IN_4") (pintype "input"))
      (node (ref "R39") (pin "2") (pinfunction "2_2") (pintype "passive"))
    )
    (net (code "103") (name "Net-(IC18-+IN)") (class "Default")
      (node (ref "IC18") (pin "3") (pinfunction "+IN_3") (pintype "input"))
      (node (ref "IC9") (pin "23") (pinfunction "VOUTC_23") (pintype "output"))
    )
    (net (code "104") (name "Net-(IC18--IN)") (class "Default")
      (node (ref "IC18") (pin "1") (pinfunction "OUT_1") (pintype "output"))
      (node (ref "IC18") (pin "4") (pinfunction "-IN_4") (pintype "input"))
      (node (ref "R45") (pin "2") (pinfunction "2_2") (pintype "passive"))
    )
    (net (code "105") (name "Net-(IC19--IN)") (class "Default")
      (node (ref "IC19") (pin "1") (pinfunction "OUT_1") (pintype "output"))
      (node (ref "IC19") (pin "4") (pinfunction "-IN_4") (pintype "input"))
      (node (ref "R69") (pin "2") (pinfunction "2_2") (pintype "passive"))
    )
    (net (code "106") (name "Net-(LED-PadA)") (class "Default")
      (node (ref "LED") (pin "A") (pinfunction "A_A") (pintype "passive"))
      (node (ref "R57") (pin "1") (pinfunction "1_1") (pintype "passive"))
    )
    (net (code "107") (name "Net-(LED1-PadA)") (class "Default")
      (node (ref "LED1") (pin "A") (pinfunction "A_A") (pintype "passive"))
      (node (ref "R21") (pin "1") (pinfunction "1_1") (pintype "passive"))
    )
    (net (code "108") (name "Net-(Q1-G)") (class "Default")
      (node (ref "Q1") (pin "1") (pinfunction "G_1") (pintype "passive"))
      (node (ref "R32") (pin "1") (pinfunction "1_1") (pintype "passive"))
      (node (ref "R34") (pin "1") (pinfunction "1_1") (pintype "passive"))
    )
    (net (code "109") (name "Net-(Q2-D)") (class "Default")
      (node (ref "Q2") (pin "3") (pinfunction "D_3") (pintype "passive"))
      (node (ref "Q3") (pin "1") (pinfunction "G_1") (pintype "passive"))
      (node (ref "R61") (pin "1") (pinfunction "1_1") (pintype "passive"))
    )
    (net (code "110") (name "Net-(R18-Pad2)") (class "Default")
      (node (ref "R18") (pin "2") (pinfunction "2_2") (pintype "passive"))
      (node (ref "X2") (pin "S2") (pinfunction "S2_S2") (pintype "passive"))
    )
    (net (code "111") (name "Net-(R31-Pad2)") (class "Default")
      (node (ref "R31") (pin "2") (pinfunction "2_2") (pintype "passive"))
      (node (ref "X4") (pin "14") (pinfunction "14_14") (pintype "passive"))
    )
    (net (code "112") (name "Net-(R33-Pad2)") (class "Default")
      (node (ref "R33") (pin "2") (pinfunction "2_2") (pintype "passive"))
      (node (ref "X4") (pin "13") (pinfunction "13_13") (pintype "passive"))
    )
    (net (code "113") (name "Net-(R35-Pad2)") (class "Default")
      (node (ref "R35") (pin "2") (pinfunction "2_2") (pintype "passive"))
      (node (ref "R36") (pin "2") (pinfunction "2_2") (pintype "passive"))
      (node (ref "R37") (pin "2") (pinfunction "2_2") (pintype "passive"))
    )
    (net (code "114") (name "Net-(R37-Pad1)") (class "Default")
      (node (ref "R37") (pin "1") (pinfunction "1_1") (pintype "passive"))
      (node (ref "R38") (pin "2") (pinfunction "2_2") (pintype "passive"))
      (node (ref "R40") (pin "2") (pinfunction "2_2") (pintype "passive"))
    )
    (net (code "115") (name "Net-(R40-Pad1)") (class "Default")
      (node (ref "R40") (pin "1") (pinfunction "1_1") (pintype "passive"))
      (node (ref "R41") (pin "2") (pinfunction "2_2") (pintype "passive"))
      (node (ref "R42") (pin "2") (pinfunction "2_2") (pintype "passive"))
    )
    (net (code "116") (name "Net-(R42-Pad1)") (class "Default")
      (node (ref "R42") (pin "1") (pinfunction "1_1") (pintype "passive"))
      (node (ref "R43") (pin "2") (pinfunction "2_2") (pintype "passive"))
      (node (ref "R46") (pin "2") (pinfunction "2_2") (pintype "passive"))
    )
    (net (code "117") (name "Net-(R46-Pad1)") (class "Default")
      (node (ref "R46") (pin "1") (pinfunction "1_1") (pintype "passive"))
      (node (ref "R47") (pin "2") (pinfunction "2_2") (pintype "passive"))
      (node (ref "R49") (pin "2") (pinfunction "2_2") (pintype "passive"))
    )
    (net (code "118") (name "Net-(R49-Pad1)") (class "Default")
      (node (ref "R49") (pin "1") (pinfunction "1_1") (pintype "passive"))
      (node (ref "R50") (pin "2") (pinfunction "2_2") (pintype "passive"))
      (node (ref "R51") (pin "2") (pinfunction "2_2") (pintype "passive"))
    )
    (net (code "119") (name "Net-(R51-Pad1)") (class "Default")
      (node (ref "R51") (pin "1") (pinfunction "1_1") (pintype "passive"))
      (node (ref "R52") (pin "2") (pinfunction "2_2") (pintype "passive"))
      (node (ref "R55") (pin "2") (pinfunction "2_2") (pintype "passive"))
    )
    (net (code "120") (name "Net-(R68-Pad1)") (class "Default")
      (node (ref "R68") (pin "1") (pinfunction "1_1") (pintype "passive"))
      (node (ref "X3") (pin "20") (pinfunction "20_20") (pintype "passive"))
    )
    (net (code "121") (name "Net-(R69-Pad1)") (class "Default")
      (node (ref "R69") (pin "1") (pinfunction "1_1") (pintype "passive"))
      (node (ref "X4") (pin "1") (pinfunction "1_1") (pintype "passive"))
      (node (ref "X4") (pin "2") (pinfunction "2_2") (pintype "passive"))
      (node (ref "X4") (pin "3") (pinfunction "3_3") (pintype "passive"))
    )
    (net (code "122") (name "Net-(SJ1-Pad2)") (class "Default")
      (node (ref "SJ1") (pin "2") (pinfunction "2_2") (pintype "passive"))
      (node (ref "X3") (pin "7") (pinfunction "7_7") (pintype "passive"))
    )
    (net (code "123") (name "OSC_CLK") (class "Default")
      (node (ref "IC8") (pin "P56") (pinfunction "IO_L30P_GCLK1_D13_2_P56") (pintype "bidirectional"))
      (node (ref "X5") (pin "3") (pinfunction "OUT_3") (pintype "output"))
    )
    (net (code "124") (name "PROGRAM") (class "Default")
      (node (ref "IC8") (pin "P37") (pinfunction "PROGRAM_B_2_P37") (pintype "input"))
      (node (ref "R53") (pin "2") (pinfunction "2_2") (pintype "passive"))
    )
    (net (code "125") (name "RAM_ADDR_0") (class "Default")
      (node (ref "IC20") (pin "3") (pinfunction "A0_3") (pintype "input"))
      (node (ref "IC8") (pin "P1") (pinfunction "IO_L83N_VREF_3_P1") (pintype "bidirectional"))
    )
    (net (code "126") (name "RAM_ADDR_1") (class "Default")
      (node (ref "IC20") (pin "4") (pinfunction "A1_4") (pintype "input"))
      (node (ref "IC8") (pin "P2") (pinfunction "IO_L83P_3_P2") (pintype "bidirectional"))
    )
    (net (code "127") (name "RAM_ADDR_2") (class "Default")
      (node (ref "IC20") (pin "5") (pinfunction "A2_5") (pintype "input"))
      (node (ref "IC8") (pin "P5") (pinfunction "IO_L52N_3_P5") (pintype "bidirectional"))
    )
    (net (code "128") (name "RAM_ADDR_3") (class "Default")
      (node (ref "IC20") (pin "6") (pinfunction "A3_6") (pintype "input"))
      (node (ref "IC8") (pin "P6") (pinfunction "IO_L52P_3_P6") (pintype "bidirectional"))
    )
    (net (code "129") (name "RAM_ADDR_4") (class "Default")
      (node (ref "IC20") (pin "7") (pinfunction "A4_7") (pintype "input"))
      (node (ref "IC8") (pin "P7") (pinfunction "IO_L51N_3_P7") (pintype "bidirectional"))
    )
    (net (code "130") (name "RAM_ADDR_5") (class "Default")
      (node (ref "IC20") (pin "16") (pinfunction "A5_16") (pintype "input"))
      (node (ref "IC8") (pin "P8") (pinfunction "IO_L51P_3_P8") (pintype "bidirectional"))
    )
    (net (code "131") (name "RAM_ADDR_6") (class "Default")
      (node (ref "IC20") (pin "17") (pinfunction "A6_17") (pintype "input"))
      (node (ref "IC8") (pin "P9") (pinfunction "IO_L50N_3_P9") (pintype "bidirectional"))
    )
    (net (code "132") (name "RAM_ADDR_7") (class "Default")
      (node (ref "IC20") (pin "18") (pinfunction "A7_18") (pintype "input"))
      (node (ref "IC8") (pin "P10") (pinfunction "IO_L50P_3_P10") (pintype "bidirectional"))
    )
    (net (code "133") (name "RAM_ADDR_8") (class "Default")
      (node (ref "IC20") (pin "19") (pinfunction "A8_19") (pintype "input"))
      (node (ref "IC8") (pin "P11") (pinfunction "IO_L49N_3_P11") (pintype "bidirectional"))
    )
    (net (code "134") (name "RAM_ADDR_9") (class "Default")
      (node (ref "IC20") (pin "20") (pinfunction "A9_20") (pintype "input"))
      (node (ref "IC8") (pin "P12") (pinfunction "IO_L49P_3_P12") (pintype "bidirectional"))
    )
    (net (code "135") (name "RAM_ADDR_10") (class "Default")
      (node (ref "IC20") (pin "26") (pinfunction "A10_26") (pintype "input"))
      (node (ref "IC8") (pin "P14") (pinfunction "IO_L44N_GCLK20_3_P14") (pintype "bidirectional"))
    )
    (net (code "136") (name "RAM_ADDR_11") (class "Default")
      (node (ref "IC20") (pin "27") (pinfunction "A11_27") (pintype "input"))
      (node (ref "IC8") (pin "P15") (pinfunction "IO_L44P_GCLK21_3_P15") (pintype "bidirectional"))
    )
    (net (code "137") (name "RAM_ADDR_12") (class "Default")
      (node (ref "IC20") (pin "28") (pinfunction "A12_28") (pintype "input"))
      (node (ref "IC8") (pin "P16") (pinfunction "IO_L43N_GCLK22_IRDY2_3_P16") (pintype "bidirectional"))
    )
    (net (code "138") (name "RAM_ADDR_13") (class "Default")
      (node (ref "IC20") (pin "29") (pinfunction "A13_29") (pintype "input"))
      (node (ref "IC8") (pin "P17") (pinfunction "IO_L43P_GCLK23_3_P17") (pintype "bidirectional"))
    )
    (net (code "139") (name "RAM_ADDR_14") (class "Default")
      (node (ref "IC20") (pin "30") (pinfunction "A14_30") (pintype "input"))
      (node (ref "IC8") (pin "P21") (pinfunction "IO_L42N_GCLK24_3_P21") (pintype "bidirectional"))
    )
    (net (code "140") (name "RAM_ADDR_15") (class "Default")
      (node (ref "IC20") (pin "38") (pinfunction "A15_38") (pintype "input"))
      (node (ref "IC8") (pin "P22") (pinfunction "IO_L42P_GCLK25_TRDY2_3_P22") (pintype "bidirectional"))
    )
    (net (code "141") (name "RAM_ADDR_16") (class "Default")
      (node (ref "IC20") (pin "39") (pinfunction "A16_39") (pintype "input"))
      (node (ref "IC8") (pin "P23") (pinfunction "IO_L41N_GCLK26_3_P23") (pintype "bidirectional"))
    )
    (net (code "142") (name "RAM_ADDR_17") (class "Default")
      (node (ref "IC20") (pin "40") (pinfunction "A17_40") (pintype "input"))
      (node (ref "IC8") (pin "P24") (pinfunction "IO_L41P_GCLK27_3_P24") (pintype "bidirectional"))
    )
    (net (code "143") (name "RAM_ADDR_18") (class "Default")
      (node (ref "IC20") (pin "41") (pinfunction "A18_41") (pintype "input"))
      (node (ref "IC8") (pin "P26") (pinfunction "IO_L37N_3_P26") (pintype "bidirectional"))
    )
    (net (code "144") (name "RAM_DATA_0") (class "Default")
      (node (ref "IC20") (pin "9") (pinfunction "I/O00_9") (pintype "bidirectional"))
      (node (ref "IC8") (pin "P143") (pinfunction "IO_L1N_VREF_0_P143") (pintype "bidirectional"))
    )
    (net (code "145") (name "RAM_DATA_1") (class "Default")
      (node (ref "IC20") (pin "10") (pinfunction "I/O01_10") (pintype "bidirectional"))
      (node (ref "IC8") (pin "P142") (pinfunction "IO_L2P_0_P142") (pintype "bidirectional"))
    )
    (net (code "146") (name "RAM_DATA_2") (class "Default")
      (node (ref "IC20") (pin "13") (pinfunction "I/O02_13") (pintype "bidirectional"))
      (node (ref "IC8") (pin "P141") (pinfunction "IO_L2N_0_P141") (pintype "bidirectional"))
    )
    (net (code "147") (name "RAM_DATA_3") (class "Default")
      (node (ref "IC20") (pin "14") (pinfunction "I/O03_14") (pintype "bidirectional"))
      (node (ref "IC8") (pin "P140") (pinfunction "IO_L3P_0_P140") (pintype "bidirectional"))
    )
    (net (code "148") (name "RAM_DATA_4") (class "Default")
      (node (ref "IC20") (pin "31") (pinfunction "I/O04_31") (pintype "bidirectional"))
      (node (ref "IC8") (pin "P134") (pinfunction "IO_L34P_GCLK19_0_P134") (pintype "bidirectional"))
    )
    (net (code "149") (name "RAM_DATA_5") (class "Default")
      (node (ref "IC20") (pin "32") (pinfunction "I/O05_32") (pintype "bidirectional"))
      (node (ref "IC8") (pin "P137") (pinfunction "IO_L4N_0_P137") (pintype "bidirectional"))
    )
    (net (code "150") (name "RAM_DATA_6") (class "Default")
      (node (ref "IC20") (pin "35") (pinfunction "I/O06_35") (pintype "bidirectional"))
      (node (ref "IC8") (pin "P138") (pinfunction "IO_L4P_0_P138") (pintype "bidirectional"))
    )
    (net (code "151") (name "RAM_DATA_7") (class "Default")
      (node (ref "IC20") (pin "36") (pinfunction "I/O07_36") (pintype "bidirectional"))
      (node (ref "IC8") (pin "P139") (pinfunction "IO_L3N_0_P139") (pintype "bidirectional"))
    )
    (net (code "152") (name "RAM_~{CE}") (class "Default")
      (node (ref "IC20") (pin "8") (pinfunction "CE_8") (pintype "input"))
      (node (ref "IC8") (pin "P30") (pinfunction "IO_L36P_3_P30") (pintype "bidirectional"))
    )
    (net (code "153") (name "RAM_~{OE}") (class "Default")
      (node (ref "IC20") (pin "37") (pinfunction "OE_37") (pintype "input"))
      (node (ref "IC8") (pin "P32") (pinfunction "IO_L2N_3_P32") (pintype "bidirectional"))
    )
    (net (code "154") (name "RAM_~{WE}") (class "Default")
      (node (ref "IC20") (pin "15") (pinfunction "WE_15") (pintype "input"))
      (node (ref "IC8") (pin "P29") (pinfunction "IO_L36N_3_P29") (pintype "bidirectional"))
    )
    (net (code "155") (name "TCK") (class "Default")
      (node (ref "IC2") (pin "38") (pinfunction "BDBUS0_38") (pintype "bidirectional"))
      (node (ref "IC8") (pin "P109") (pinfunction "TCK_P109") (pintype "input"))
    )
    (net (code "156") (name "TDI") (class "Default")
      (node (ref "IC2") (pin "39") (pinfunction "BDBUS1_39") (pintype "bidirectional"))
      (node (ref "IC8") (pin "P110") (pinfunction "TDI_P110") (pintype "input"))
    )
    (net (code "157") (name "TDO") (class "Default")
      (node (ref "IC2") (pin "40") (pinfunction "BDBUS2_40") (pintype "bidirectional"))
      (node (ref "IC8") (pin "P106") (pinfunction "TDO_P106") (pintype "output"))
    )
    (net (code "158") (name "TMS") (class "Default")
      (node (ref "IC2") (pin "41") (pinfunction "BDBUS3_41") (pintype "bidirectional"))
      (node (ref "IC8") (pin "P107") (pinfunction "TMS_P107") (pintype "input"))
    )
    (net (code "159") (name "USB_DM") (class "Default")
      (node (ref "D1") (pin "3") (pinfunction "IO2_3") (pintype "passive"))
      (node (ref "R10") (pin "1") (pinfunction "1_1") (pintype "passive"))
      (node (ref "X2") (pin "2") (pinfunction "2_2") (pintype "passive"))
    )
    (net (code "160") (name "USB_DP") (class "Default")
      (node (ref "D1") (pin "2") (pinfunction "IO1_2") (pintype "passive"))
      (node (ref "R11") (pin "1") (pinfunction "1_1") (pintype "passive"))
      (node (ref "X2") (pin "3") (pinfunction "3_3") (pintype "passive"))
    )
    (net (code "161") (name "USER_LED") (class "Default")
      (node (ref "IC8") (pin "P55") (pinfunction "IO_L30N_GCLK0_USERCCLK_2_P55") (pintype "bidirectional"))
      (node (ref "R57") (pin "2") (pinfunction "2_2") (pintype "passive"))
    )
    (net (code "162") (name "VGA_3V3") (class "Default")
      (node (ref "IC19") (pin "3") (pinfunction "+IN_3") (pintype "input"))
      (node (ref "R55") (pin "1") (pinfunction "1_1") (pintype "passive"))
      (node (ref "R56") (pin "2") (pinfunction "2_2") (pintype "passive"))
    )
    (net (code "163") (name "VGA_G0") (class "Default")
      (node (ref "IC8") (pin "P51") (pinfunction "IO_L31P_GCLK31_D14_2_P51") (pintype "bidirectional"))
      (node (ref "R36") (pin "1") (pinfunction "1_1") (pintype "passive"))
    )
    (net (code "164") (name "VGA_G1") (class "Default")
      (node (ref "IC8") (pin "P50") (pinfunction "IO_L31N_GCLK30_D15_2_P50") (pintype "bidirectional"))
      (node (ref "R38") (pin "1") (pinfunction "1_1") (pintype "passive"))
    )
    (net (code "165") (name "VGA_G2") (class "Default")
      (node (ref "IC8") (pin "P48") (pinfunction "IO_L48P_D7_2_P48") (pintype "bidirectional"))
      (node (ref "R41") (pin "1") (pinfunction "1_1") (pintype "passive"))
    )
    (net (code "166") (name "VGA_G3") (class "Default")
      (node (ref "IC8") (pin "P47") (pinfunction "IO_L48N_RDWR_B_VREF_2_P47") (pintype "bidirectional"))
      (node (ref "R43") (pin "1") (pinfunction "1_1") (pintype "passive"))
    )
    (net (code "167") (name "VGA_G4") (class "Default")
      (node (ref "IC8") (pin "P46") (pinfunction "IO_L49P_D3_2_P46") (pintype "bidirectional"))
      (node (ref "R47") (pin "1") (pinfunction "1_1") (pintype "passive"))
    )
    (net (code "168") (name "VGA_G5") (class "Default")
      (node (ref "IC8") (pin "P45") (pinfunction "IO_L49N_D4_2_P45") (pintype "bidirectional"))
      (node (ref "R50") (pin "1") (pinfunction "1_1") (pintype "passive"))
    )
    (net (code "169") (name "VGA_G6") (class "Default")
      (node (ref "IC8") (pin "P44") (pinfunction "IO_L62P_D5_2_P44") (pintype "bidirectional"))
      (node (ref "R52") (pin "1") (pinfunction "1_1") (pintype "passive"))
    )
    (net (code "170") (name "VGA_G7") (class "Default")
      (node (ref "IC8") (pin "P43") (pinfunction "IO_L62N_D6_2_P43") (pintype "bidirectional"))
      (node (ref "R56") (pin "1") (pinfunction "1_1") (pintype "passive"))
    )
    (net (code "171") (name "VGA_HSYNC") (class "Default")
      (node (ref "IC8") (pin "P40") (pinfunction "IO_L64N_D9_2_P40") (pintype "bidirectional"))
      (node (ref "R33") (pin "1") (pinfunction "1_1") (pintype "passive"))
    )
    (net (code "172") (name "VGA_VSYNC") (class "Default")
      (node (ref "IC8") (pin "P41") (pinfunction "IO_L64P_D8_2_P41") (pintype "bidirectional"))
      (node (ref "R31") (pin "1") (pinfunction "1_1") (pintype "passive"))
    )
    (net (code "173") (name "VIDEO_0") (class "Default")
      (node (ref "D4") (pin "C") (pinfunction "C_C") (pintype "passive"))
      (node (ref "R29") (pin "2") (pinfunction "2_2") (pintype "passive"))
      (node (ref "SJ1") (pin "1") (pinfunction "1_1") (pintype "passive"))
    )
    (net (code "174") (name "VIDEO_1") (class "Default")
      (node (ref "D2") (pin "C") (pinfunction "C_C") (pintype "passive"))
      (node (ref "R14") (pin "2") (pinfunction "2_2") (pintype "passive"))
      (node (ref "X3") (pin "2") (pinfunction "2_2") (pintype "passive"))
    )
    (net (code "175") (name "V_BUS") (class "Default")
      (node (ref "C7") (pin "1") (pinfunction "1_1") (pintype "passive"))
      (node (ref "D1") (pin "4") (pinfunction "VCC_4") (pintype "passive"))
      (node (ref "F1") (pin "2") (pinfunction "2_2") (pintype "passive"))
      (node (ref "R6") (pin "1") (pinfunction "1_1") (pintype "passive"))
      (node (ref "X2") (pin "1") (pinfunction "1_1") (pintype "passive"))
    )
    (net (code "176") (name "X_CMD") (class "Default")
      (node (ref "D5") (pin "C") (pinfunction "C_C") (pintype "passive"))
      (node (ref "R39") (pin "1") (pinfunction "1_1") (pintype "passive"))
      (node (ref "X3") (pin "10") (pinfunction "10_10") (pintype "passive"))
    )
    (net (code "177") (name "Y_CMD") (class "Default")
      (node (ref "D6") (pin "C") (pinfunction "C_C") (pintype "passive"))
      (node (ref "R45") (pin "1") (pinfunction "1_1") (pintype "passive"))
      (node (ref "X3") (pin "13") (pinfunction "13_13") (pintype "passive"))
    )
    (net (code "178") (name "unconnected-(IC2-ACBUS7-Pad34)") (class "Default")
      (node (ref "IC2") (pin "34") (pinfunction "ACBUS7_34") (pintype "bidirectional"))
    )
    (net (code "179") (name "unconnected-(IC2-BCBUS0-Pad48)") (class "Default")
      (node (ref "IC2") (pin "48") (pinfunction "BCBUS0_48") (pintype "bidirectional"))
    )
    (net (code "180") (name "unconnected-(IC2-BCBUS1-Pad52)") (class "Default")
      (node (ref "IC2") (pin "52") (pinfunction "BCBUS1_52") (pintype "bidirectional"))
    )
    (net (code "181") (name "unconnected-(IC2-BCBUS2-Pad53)") (class "Default")
      (node (ref "IC2") (pin "53") (pinfunction "BCBUS2_53") (pintype "bidirectional"))
    )
    (net (code "182") (name "unconnected-(IC2-BCBUS3-Pad54)") (class "Default")
      (node (ref "IC2") (pin "54") (pinfunction "BCBUS3_54") (pintype "bidirectional"))
    )
    (net (code "183") (name "unconnected-(IC2-BCBUS4-Pad55)") (class "Default")
      (node (ref "IC2") (pin "55") (pinfunction "BCBUS4_55") (pintype "bidirectional"))
    )
    (net (code "184") (name "unconnected-(IC2-BCBUS5-Pad57)") (class "Default")
      (node (ref "IC2") (pin "57") (pinfunction "BCBUS5_57") (pintype "bidirectional"))
    )
    (net (code "185") (name "unconnected-(IC2-BCBUS6-Pad58)") (class "Default")
      (node (ref "IC2") (pin "58") (pinfunction "BCBUS6_58") (pintype "bidirectional"))
    )
    (net (code "186") (name "unconnected-(IC2-BDBUS4-Pad43)") (class "Default")
      (node (ref "IC2") (pin "43") (pinfunction "BDBUS4_43") (pintype "bidirectional"))
    )
    (net (code "187") (name "unconnected-(IC2-BDBUS5-Pad44)") (class "Default")
      (node (ref "IC2") (pin "44") (pinfunction "BDBUS5_44") (pintype "bidirectional"))
    )
    (net (code "188") (name "unconnected-(IC2-BDBUS6-Pad45)") (class "Default")
      (node (ref "IC2") (pin "45") (pinfunction "BDBUS6_45") (pintype "bidirectional"))
    )
    (net (code "189") (name "unconnected-(IC2-BDBUS7-Pad46)") (class "Default")
      (node (ref "IC2") (pin "46") (pinfunction "BDBUS7_46") (pintype "bidirectional"))
    )
    (net (code "190") (name "unconnected-(IC3-DIS-Pad7)") (class "Default")
      (node (ref "IC3") (pin "7") (pinfunction "DIS_7") (pintype "passive"))
    )
    (net (code "191") (name "unconnected-(IC7-DIS-Pad7)") (class "Default")
      (node (ref "IC7") (pin "7") (pinfunction "DIS_7") (pintype "passive"))
    )
    (net (code "192") (name "unconnected-(IC8B-IO_L1N_VREF_1-PadP104)") (class "Default")
      (node (ref "IC8") (pin "P104") (pinfunction "IO_L1N_VREF_1_P104") (pintype "bidirectional"))
    )
    (net (code "193") (name "unconnected-(IC8B-IO_L1P_1-PadP105)") (class "Default")
      (node (ref "IC8") (pin "P105") (pinfunction "IO_L1P_1_P105") (pintype "bidirectional"))
    )
    (net (code "194") (name "unconnected-(IC8B-IO_L43N_GCLK4_1-PadP84)") (class "Default")
      (node (ref "IC8") (pin "P84") (pinfunction "IO_L43N_GCLK4_1_P84") (pintype "bidirectional"))
    )
    (net (code "195") (name "unconnected-(IC8B-IO_L45P_1-PadP83)") (class "Default")
      (node (ref "IC8") (pin "P83") (pinfunction "IO_L45P_1_P83") (pintype "bidirectional"))
    )
    (net (code "196") (name "unconnected-(IC8B-IO_L74N_DOUT_BUSY_1-PadP74)") (class "Default")
      (node (ref "IC8") (pin "P74") (pinfunction "IO_L74N_DOUT_BUSY_1_P74") (pintype "bidirectional"))
    )
    (net (code "197") (name "unconnected-(IC8C-IO_L2N_CMPMOSI_2-PadP66)") (class "Default")
      (node (ref "IC8") (pin "P66") (pinfunction "IO_L2N_CMPMOSI_2_P66") (pintype "bidirectional"))
    )
    (net (code "198") (name "unconnected-(IC8C-IO_L2P_CMPCLK_2-PadP67)") (class "Default")
      (node (ref "IC8") (pin "P67") (pinfunction "IO_L2P_CMPCLK_2_P67") (pintype "bidirectional"))
    )
    (net (code "199") (name "unconnected-(IC8C-IO_L12N_D2_MISO3_2-PadP61)") (class "Default")
      (node (ref "IC8") (pin "P61") (pinfunction "IO_L12N_D2_MISO3_2_P61") (pintype "bidirectional"))
    )
    (net (code "200") (name "unconnected-(IC8C-IO_L14N_D12_2-PadP57)") (class "Default")
      (node (ref "IC8") (pin "P57") (pinfunction "IO_L14N_D12_2_P57") (pintype "bidirectional"))
    )
    (net (code "201") (name "unconnected-(IC8D-IO_L1N_VREF_3-PadP34)") (class "Default")
      (node (ref "IC8") (pin "P34") (pinfunction "IO_L1N_VREF_3_P34") (pintype "bidirectional"))
    )
    (net (code "202") (name "unconnected-(IC8D-IO_L1P_3-PadP35)") (class "Default")
      (node (ref "IC8") (pin "P35") (pinfunction "IO_L1P_3_P35") (pintype "bidirectional"))
    )
    (net (code "203") (name "unconnected-(IC8D-IO_L2P_3-PadP33)") (class "Default")
      (node (ref "IC8") (pin "P33") (pinfunction "IO_L2P_3_P33") (pintype "bidirectional"))
    )
    (net (code "204") (name "unconnected-(IC8D-IO_L37P_3-PadP27)") (class "Default")
      (node (ref "IC8") (pin "P27") (pinfunction "IO_L37P_3_P27") (pintype "bidirectional"))
    )
    (net (code "205") (name "unconnected-(IC9-VOUTB-Pad4)") (class "Default")
      (node (ref "IC9") (pin "4") (pinfunction "VOUTB_4") (pintype "output"))
    )
    (net (code "206") (name "unconnected-(IC9-VOUTD-Pad22)") (class "Default")
      (node (ref "IC9") (pin "22") (pinfunction "VOUTD_22") (pintype "output"))
    )
    (net (code "207") (name "unconnected-(X3-Pad3)") (class "Default")
      (node (ref "X3") (pin "3") (pinfunction "3_3") (pintype "passive"))
    )
    (net (code "208") (name "unconnected-(X3-Pad4)") (class "Default")
      (node (ref "X3") (pin "4") (pinfunction "4_4") (pintype "passive"))
    )
    (net (code "209") (name "unconnected-(X3-Pad5)") (class "Default")
      (node (ref "X3") (pin "5") (pinfunction "5_5") (pintype "passive"))
    )
    (net (code "210") (name "unconnected-(X3-Pad6)") (class "Default")
      (node (ref "X3") (pin "6") (pinfunction "6_6") (pintype "passive"))
    )
    (net (code "211") (name "unconnected-(X3-Pad8)") (class "Default")
      (node (ref "X3") (pin "8") (pinfunction "8_8") (pintype "passive"))
    )
    (net (code "212") (name "unconnected-(X3-Pad11)") (class "Default")
      (node (ref "X3") (pin "11") (pinfunction "11_11") (pintype "passive"))
    )
    (net (code "213") (name "unconnected-(X3-Pad14)") (class "Default")
      (node (ref "X3") (pin "14") (pinfunction "14_14") (pintype "passive"))
    )
    (net (code "214") (name "unconnected-(X3-Pad15)") (class "Default")
      (node (ref "X3") (pin "15") (pinfunction "15_15") (pintype "passive"))
    )
    (net (code "215") (name "unconnected-(X3-Pad16)") (class "Default")
      (node (ref "X3") (pin "16") (pinfunction "16_16") (pintype "passive"))
    )
    (net (code "216") (name "unconnected-(X3-Pad17)") (class "Default")
      (node (ref "X3") (pin "17") (pinfunction "17_17") (pintype "passive"))
    )
    (net (code "217") (name "unconnected-(X3-Pad18)") (class "Default")
      (node (ref "X3") (pin "18") (pinfunction "18_18") (pintype "passive"))
    )
    (net (code "218") (name "unconnected-(X3-Pad19)") (class "Default")
      (node (ref "X3") (pin "19") (pinfunction "19_19") (pintype "passive"))
    )
    (net (code "219") (name "unconnected-(X3-Pad21)") (class "Default")
      (node (ref "X3") (pin "21") (pinfunction "21_21") (pintype "passive"))
    )
    (net (code "220") (name "unconnected-(X3-Pad22)") (class "Default")
      (node (ref "X3") (pin "22") (pinfunction "22_22") (pintype "passive"))
    )
    (net (code "221") (name "unconnected-(X3-Pad23)") (class "Default")
      (node (ref "X3") (pin "23") (pinfunction "23_23") (pintype "passive"))
    )
    (net (code "222") (name "unconnected-(X3-Pad24)") (class "Default")
      (node (ref "X3") (pin "24") (pinfunction "24_24") (pintype "passive"))
    )
    (net (code "223") (name "unconnected-(X3-Pad25)") (class "Default")
      (node (ref "X3") (pin "25") (pinfunction "25_25") (pintype "passive"))
    )
    (net (code "224") (name "unconnected-(X4-Pad4)") (class "Default")
      (node (ref "X4") (pin "4") (pinfunction "4_4") (pintype "passive"))
    )
    (net (code "225") (name "unconnected-(X4-Pad9)") (class "Default")
      (node (ref "X4") (pin "9") (pinfunction "9_9") (pintype "passive"))
    )
    (net (code "226") (name "unconnected-(X4-Pad11)") (class "Default")
      (node (ref "X4") (pin "11") (pinfunction "11_11") (pintype "passive"))
    )
    (net (code "227") (name "unconnected-(X4-Pad12)") (class "Default")
      (node (ref "X4") (pin "12") (pinfunction "12_12") (pintype "passive"))
    )
    (net (code "228") (name "unconnected-(X4-Pad15)") (class "Default")
      (node (ref "X4") (pin "15") (pinfunction "15_15") (pintype "passive"))
    )
    (net (code "229") (name "~{CONTROL}") (class "Default")
      (node (ref "Q1") (pin "3") (pinfunction "D_3") (pintype "passive"))
      (node (ref "R68") (pin "2") (pinfunction "2_2") (pintype "passive"))
    )
    (net (code "230") (name "~{PWREN}") (class "Default")
      (node (ref "IC2") (pin "60") (pinfunction "PWREN#_60") (pintype "bidirectional"))
      (node (ref "IC8") (pin "P112") (pinfunction "IO_L66P_SCP1_0_P112") (pintype "bidirectional"))
    )
    (net (code "231") (name "~{PWRSAV}") (class "Default")
      (node (ref "IC2") (pin "59") (pinfunction "BCBUS7_59") (pintype "bidirectional"))
      (node (ref "R2") (pin "2") (pinfunction "2_2") (pintype "passive"))
      (node (ref "R6") (pin "2") (pinfunction "2_2") (pintype "passive"))
    )
    (net (code "232") (name "~{SUSPEND}") (class "Default")
      (node (ref "IC2") (pin "36") (pinfunction "SUSPEND#_36") (pintype "bidirectional"))
      (node (ref "IC8") (pin "P111") (pinfunction "IO_L66N_SCP0_0_P111") (pintype "bidirectional"))
    )
  )
)
